# LED_Board.net
KiCad netlist of a schematic drawn in EAGLE
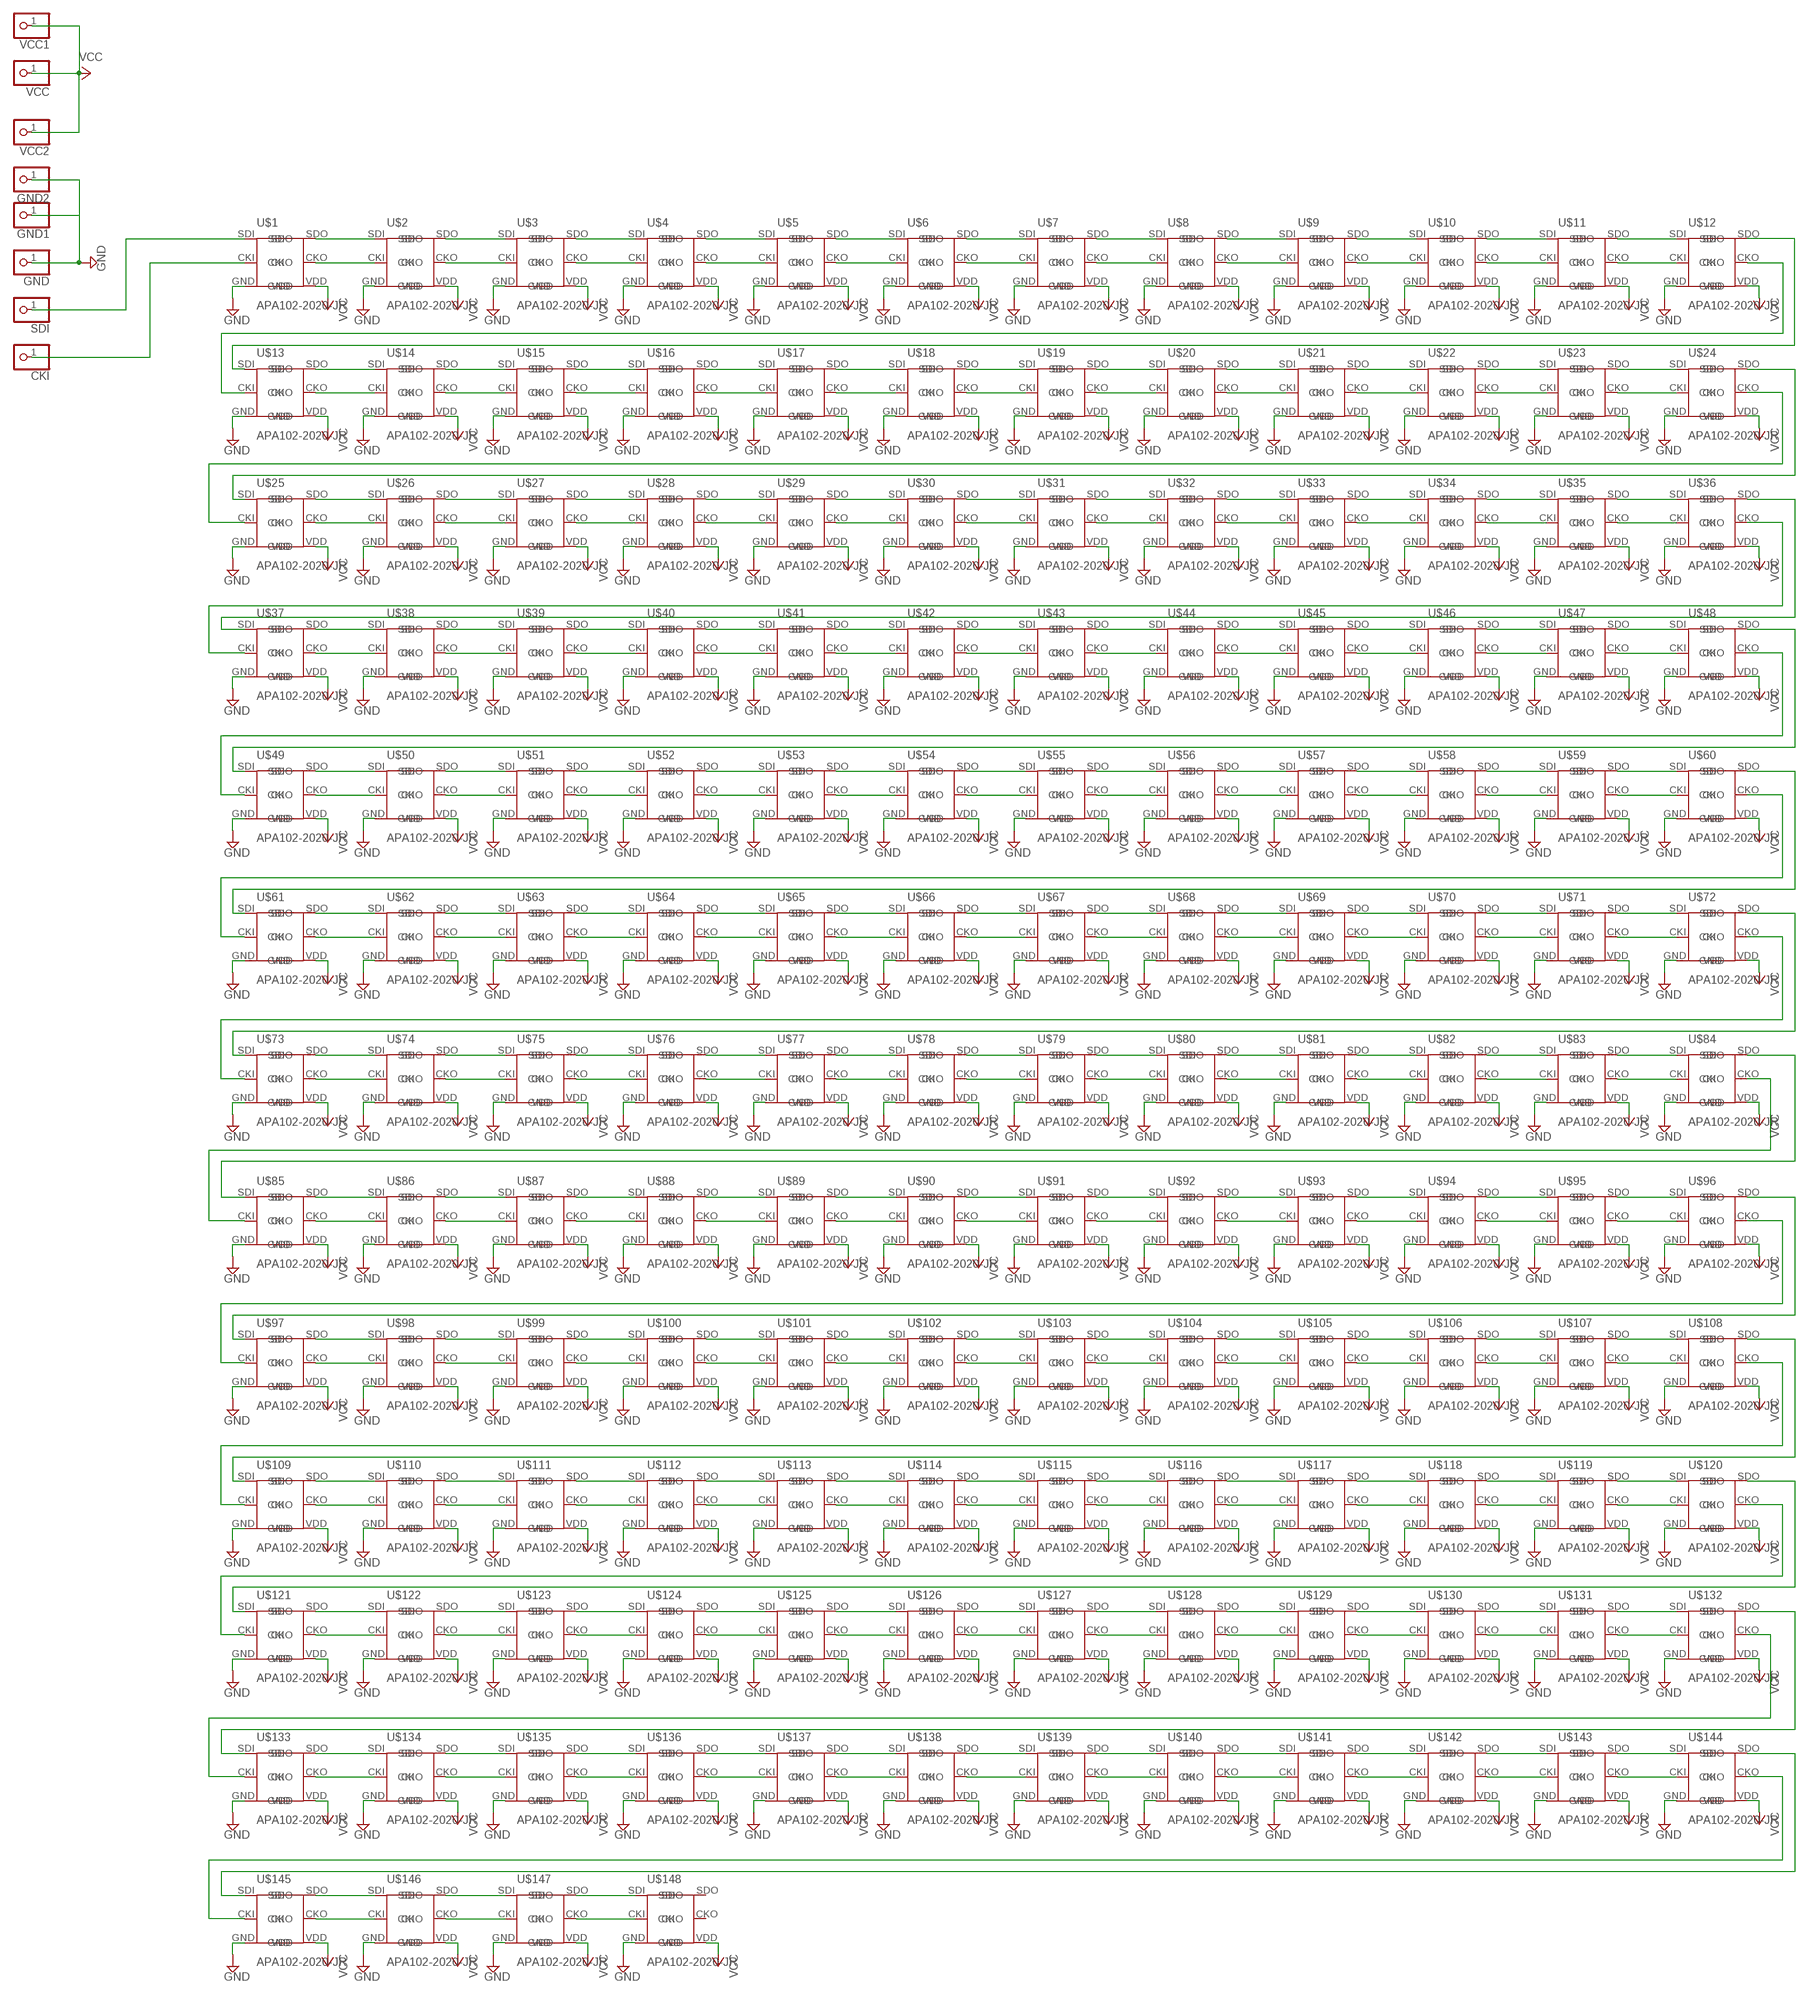
[diagram p0: schematic, sheet 1]

(export (version "E")
  (design (tool "Eeschema 10.0.6"))
  (components
    (comp (ref "CKI")
      (value "PINHD-1X1")
      (footprint "eagle-import:1X01")
      (libsource (lib "eagle-import") (part "PINHD-1X1"))
    )
    (comp (ref "GND")
      (value "PINHD-1X1")
      (footprint "eagle-import:1X01")
      (libsource (lib "eagle-import") (part "PINHD-1X1"))
    )
    (comp (ref "GND1")
      (value "PINHD-1X1")
      (footprint "eagle-import:1X01")
      (libsource (lib "eagle-import") (part "PINHD-1X1"))
    )
    (comp (ref "GND2")
      (value "PINHD-1X1")
      (footprint "eagle-import:1X01")
      (libsource (lib "eagle-import") (part "PINHD-1X1"))
    )
    (comp (ref "SDI")
      (value "PINHD-1X1")
      (footprint "eagle-import:1X01")
      (libsource (lib "eagle-import") (part "PINHD-1X1"))
    )
    (comp (ref "U$1")
      (value "APA102-2020-JR")
      (footprint "eagle-import:APA102-2020-JR")
      (libsource (lib "eagle-import") (part "APA102-2020-JR"))
    )
    (comp (ref "U$2")
      (value "APA102-2020-JR")
      (footprint "eagle-import:APA102-2020-JR")
      (libsource (lib "eagle-import") (part "APA102-2020-JR"))
    )
    (comp (ref "U$3")
      (value "APA102-2020-JR")
      (footprint "eagle-import:APA102-2020-JR")
      (libsource (lib "eagle-import") (part "APA102-2020-JR"))
    )
    (comp (ref "U$4")
      (value "APA102-2020-JR")
      (footprint "eagle-import:APA102-2020-JR")
      (libsource (lib "eagle-import") (part "APA102-2020-JR"))
    )
    (comp (ref "U$5")
      (value "APA102-2020-JR")
      (footprint "eagle-import:APA102-2020-JR")
      (libsource (lib "eagle-import") (part "APA102-2020-JR"))
    )
    (comp (ref "U$6")
      (value "APA102-2020-JR")
      (footprint "eagle-import:APA102-2020-JR")
      (libsource (lib "eagle-import") (part "APA102-2020-JR"))
    )
    (comp (ref "U$7")
      (value "APA102-2020-JR")
      (footprint "eagle-import:APA102-2020-JR")
      (libsource (lib "eagle-import") (part "APA102-2020-JR"))
    )
    (comp (ref "U$8")
      (value "APA102-2020-JR")
      (footprint "eagle-import:APA102-2020-JR")
      (libsource (lib "eagle-import") (part "APA102-2020-JR"))
    )
    (comp (ref "U$9")
      (value "APA102-2020-JR")
      (footprint "eagle-import:APA102-2020-JR")
      (libsource (lib "eagle-import") (part "APA102-2020-JR"))
    )
    (comp (ref "U$10")
      (value "APA102-2020-JR")
      (footprint "eagle-import:APA102-2020-JR")
      (libsource (lib "eagle-import") (part "APA102-2020-JR"))
    )
    (comp (ref "U$11")
      (value "APA102-2020-JR")
      (footprint "eagle-import:APA102-2020-JR")
      (libsource (lib "eagle-import") (part "APA102-2020-JR"))
    )
    (comp (ref "U$12")
      (value "APA102-2020-JR")
      (footprint "eagle-import:APA102-2020-JR")
      (libsource (lib "eagle-import") (part "APA102-2020-JR"))
    )
    (comp (ref "U$13")
      (value "APA102-2020-JR")
      (footprint "eagle-import:APA102-2020-JR")
      (libsource (lib "eagle-import") (part "APA102-2020-JR"))
    )
    (comp (ref "U$14")
      (value "APA102-2020-JR")
      (footprint "eagle-import:APA102-2020-JR")
      (libsource (lib "eagle-import") (part "APA102-2020-JR"))
    )
    (comp (ref "U$15")
      (value "APA102-2020-JR")
      (footprint "eagle-import:APA102-2020-JR")
      (libsource (lib "eagle-import") (part "APA102-2020-JR"))
    )
    (comp (ref "U$16")
      (value "APA102-2020-JR")
      (footprint "eagle-import:APA102-2020-JR")
      (libsource (lib "eagle-import") (part "APA102-2020-JR"))
    )
    (comp (ref "U$17")
      (value "APA102-2020-JR")
      (footprint "eagle-import:APA102-2020-JR")
      (libsource (lib "eagle-import") (part "APA102-2020-JR"))
    )
    (comp (ref "U$18")
      (value "APA102-2020-JR")
      (footprint "eagle-import:APA102-2020-JR")
      (libsource (lib "eagle-import") (part "APA102-2020-JR"))
    )
    (comp (ref "U$19")
      (value "APA102-2020-JR")
      (footprint "eagle-import:APA102-2020-JR")
      (libsource (lib "eagle-import") (part "APA102-2020-JR"))
    )
    (comp (ref "U$20")
      (value "APA102-2020-JR")
      (footprint "eagle-import:APA102-2020-JR")
      (libsource (lib "eagle-import") (part "APA102-2020-JR"))
    )
    (comp (ref "U$21")
      (value "APA102-2020-JR")
      (footprint "eagle-import:APA102-2020-JR")
      (libsource (lib "eagle-import") (part "APA102-2020-JR"))
    )
    (comp (ref "U$22")
      (value "APA102-2020-JR")
      (footprint "eagle-import:APA102-2020-JR")
      (libsource (lib "eagle-import") (part "APA102-2020-JR"))
    )
    (comp (ref "U$23")
      (value "APA102-2020-JR")
      (footprint "eagle-import:APA102-2020-JR")
      (libsource (lib "eagle-import") (part "APA102-2020-JR"))
    )
    (comp (ref "U$24")
      (value "APA102-2020-JR")
      (footprint "eagle-import:APA102-2020-JR")
      (libsource (lib "eagle-import") (part "APA102-2020-JR"))
    )
    (comp (ref "U$25")
      (value "APA102-2020-JR")
      (footprint "eagle-import:APA102-2020-JR")
      (libsource (lib "eagle-import") (part "APA102-2020-JR"))
    )
    (comp (ref "U$26")
      (value "APA102-2020-JR")
      (footprint "eagle-import:APA102-2020-JR")
      (libsource (lib "eagle-import") (part "APA102-2020-JR"))
    )
    (comp (ref "U$27")
      (value "APA102-2020-JR")
      (footprint "eagle-import:APA102-2020-JR")
      (libsource (lib "eagle-import") (part "APA102-2020-JR"))
    )
    (comp (ref "U$28")
      (value "APA102-2020-JR")
      (footprint "eagle-import:APA102-2020-JR")
      (libsource (lib "eagle-import") (part "APA102-2020-JR"))
    )
    (comp (ref "U$29")
      (value "APA102-2020-JR")
      (footprint "eagle-import:APA102-2020-JR")
      (libsource (lib "eagle-import") (part "APA102-2020-JR"))
    )
    (comp (ref "U$30")
      (value "APA102-2020-JR")
      (footprint "eagle-import:APA102-2020-JR")
      (libsource (lib "eagle-import") (part "APA102-2020-JR"))
    )
    (comp (ref "U$31")
      (value "APA102-2020-JR")
      (footprint "eagle-import:APA102-2020-JR")
      (libsource (lib "eagle-import") (part "APA102-2020-JR"))
    )
    (comp (ref "U$32")
      (value "APA102-2020-JR")
      (footprint "eagle-import:APA102-2020-JR")
      (libsource (lib "eagle-import") (part "APA102-2020-JR"))
    )
    (comp (ref "U$33")
      (value "APA102-2020-JR")
      (footprint "eagle-import:APA102-2020-JR")
      (libsource (lib "eagle-import") (part "APA102-2020-JR"))
    )
    (comp (ref "U$34")
      (value "APA102-2020-JR")
      (footprint "eagle-import:APA102-2020-JR")
      (libsource (lib "eagle-import") (part "APA102-2020-JR"))
    )
    (comp (ref "U$35")
      (value "APA102-2020-JR")
      (footprint "eagle-import:APA102-2020-JR")
      (libsource (lib "eagle-import") (part "APA102-2020-JR"))
    )
    (comp (ref "U$36")
      (value "APA102-2020-JR")
      (footprint "eagle-import:APA102-2020-JR")
      (libsource (lib "eagle-import") (part "APA102-2020-JR"))
    )
    (comp (ref "U$37")
      (value "APA102-2020-JR")
      (footprint "eagle-import:APA102-2020-JR")
      (libsource (lib "eagle-import") (part "APA102-2020-JR"))
    )
    (comp (ref "U$38")
      (value "APA102-2020-JR")
      (footprint "eagle-import:APA102-2020-JR")
      (libsource (lib "eagle-import") (part "APA102-2020-JR"))
    )
    (comp (ref "U$39")
      (value "APA102-2020-JR")
      (footprint "eagle-import:APA102-2020-JR")
      (libsource (lib "eagle-import") (part "APA102-2020-JR"))
    )
    (comp (ref "U$40")
      (value "APA102-2020-JR")
      (footprint "eagle-import:APA102-2020-JR")
      (libsource (lib "eagle-import") (part "APA102-2020-JR"))
    )
    (comp (ref "U$41")
      (value "APA102-2020-JR")
      (footprint "eagle-import:APA102-2020-JR")
      (libsource (lib "eagle-import") (part "APA102-2020-JR"))
    )
    (comp (ref "U$42")
      (value "APA102-2020-JR")
      (footprint "eagle-import:APA102-2020-JR")
      (libsource (lib "eagle-import") (part "APA102-2020-JR"))
    )
    (comp (ref "U$43")
      (value "APA102-2020-JR")
      (footprint "eagle-import:APA102-2020-JR")
      (libsource (lib "eagle-import") (part "APA102-2020-JR"))
    )
    (comp (ref "U$44")
      (value "APA102-2020-JR")
      (footprint "eagle-import:APA102-2020-JR")
      (libsource (lib "eagle-import") (part "APA102-2020-JR"))
    )
    (comp (ref "U$45")
      (value "APA102-2020-JR")
      (footprint "eagle-import:APA102-2020-JR")
      (libsource (lib "eagle-import") (part "APA102-2020-JR"))
    )
    (comp (ref "U$46")
      (value "APA102-2020-JR")
      (footprint "eagle-import:APA102-2020-JR")
      (libsource (lib "eagle-import") (part "APA102-2020-JR"))
    )
    (comp (ref "U$47")
      (value "APA102-2020-JR")
      (footprint "eagle-import:APA102-2020-JR")
      (libsource (lib "eagle-import") (part "APA102-2020-JR"))
    )
    (comp (ref "U$48")
      (value "APA102-2020-JR")
      (footprint "eagle-import:APA102-2020-JR")
      (libsource (lib "eagle-import") (part "APA102-2020-JR"))
    )
    (comp (ref "U$49")
      (value "APA102-2020-JR")
      (footprint "eagle-import:APA102-2020-JR")
      (libsource (lib "eagle-import") (part "APA102-2020-JR"))
    )
    (comp (ref "U$50")
      (value "APA102-2020-JR")
      (footprint "eagle-import:APA102-2020-JR")
      (libsource (lib "eagle-import") (part "APA102-2020-JR"))
    )
    (comp (ref "U$51")
      (value "APA102-2020-JR")
      (footprint "eagle-import:APA102-2020-JR")
      (libsource (lib "eagle-import") (part "APA102-2020-JR"))
    )
    (comp (ref "U$52")
      (value "APA102-2020-JR")
      (footprint "eagle-import:APA102-2020-JR")
      (libsource (lib "eagle-import") (part "APA102-2020-JR"))
    )
    (comp (ref "U$53")
      (value "APA102-2020-JR")
      (footprint "eagle-import:APA102-2020-JR")
      (libsource (lib "eagle-import") (part "APA102-2020-JR"))
    )
    (comp (ref "U$54")
      (value "APA102-2020-JR")
      (footprint "eagle-import:APA102-2020-JR")
      (libsource (lib "eagle-import") (part "APA102-2020-JR"))
    )
    (comp (ref "U$55")
      (value "APA102-2020-JR")
      (footprint "eagle-import:APA102-2020-JR")
      (libsource (lib "eagle-import") (part "APA102-2020-JR"))
    )
    (comp (ref "U$56")
      (value "APA102-2020-JR")
      (footprint "eagle-import:APA102-2020-JR")
      (libsource (lib "eagle-import") (part "APA102-2020-JR"))
    )
    (comp (ref "U$57")
      (value "APA102-2020-JR")
      (footprint "eagle-import:APA102-2020-JR")
      (libsource (lib "eagle-import") (part "APA102-2020-JR"))
    )
    (comp (ref "U$58")
      (value "APA102-2020-JR")
      (footprint "eagle-import:APA102-2020-JR")
      (libsource (lib "eagle-import") (part "APA102-2020-JR"))
    )
    (comp (ref "U$59")
      (value "APA102-2020-JR")
      (footprint "eagle-import:APA102-2020-JR")
      (libsource (lib "eagle-import") (part "APA102-2020-JR"))
    )
    (comp (ref "U$60")
      (value "APA102-2020-JR")
      (footprint "eagle-import:APA102-2020-JR")
      (libsource (lib "eagle-import") (part "APA102-2020-JR"))
    )
    (comp (ref "U$61")
      (value "APA102-2020-JR")
      (footprint "eagle-import:APA102-2020-JR")
      (libsource (lib "eagle-import") (part "APA102-2020-JR"))
    )
    (comp (ref "U$62")
      (value "APA102-2020-JR")
      (footprint "eagle-import:APA102-2020-JR")
      (libsource (lib "eagle-import") (part "APA102-2020-JR"))
    )
    (comp (ref "U$63")
      (value "APA102-2020-JR")
      (footprint "eagle-import:APA102-2020-JR")
      (libsource (lib "eagle-import") (part "APA102-2020-JR"))
    )
    (comp (ref "U$64")
      (value "APA102-2020-JR")
      (footprint "eagle-import:APA102-2020-JR")
      (libsource (lib "eagle-import") (part "APA102-2020-JR"))
    )
    (comp (ref "U$65")
      (value "APA102-2020-JR")
      (footprint "eagle-import:APA102-2020-JR")
      (libsource (lib "eagle-import") (part "APA102-2020-JR"))
    )
    (comp (ref "U$66")
      (value "APA102-2020-JR")
      (footprint "eagle-import:APA102-2020-JR")
      (libsource (lib "eagle-import") (part "APA102-2020-JR"))
    )
    (comp (ref "U$67")
      (value "APA102-2020-JR")
      (footprint "eagle-import:APA102-2020-JR")
      (libsource (lib "eagle-import") (part "APA102-2020-JR"))
    )
    (comp (ref "U$68")
      (value "APA102-2020-JR")
      (footprint "eagle-import:APA102-2020-JR")
      (libsource (lib "eagle-import") (part "APA102-2020-JR"))
    )
    (comp (ref "U$69")
      (value "APA102-2020-JR")
      (footprint "eagle-import:APA102-2020-JR")
      (libsource (lib "eagle-import") (part "APA102-2020-JR"))
    )
    (comp (ref "U$70")
      (value "APA102-2020-JR")
      (footprint "eagle-import:APA102-2020-JR")
      (libsource (lib "eagle-import") (part "APA102-2020-JR"))
    )
    (comp (ref "U$71")
      (value "APA102-2020-JR")
      (footprint "eagle-import:APA102-2020-JR")
      (libsource (lib "eagle-import") (part "APA102-2020-JR"))
    )
    (comp (ref "U$72")
      (value "APA102-2020-JR")
      (footprint "eagle-import:APA102-2020-JR")
      (libsource (lib "eagle-import") (part "APA102-2020-JR"))
    )
    (comp (ref "U$73")
      (value "APA102-2020-JR")
      (footprint "eagle-import:APA102-2020-JR")
      (libsource (lib "eagle-import") (part "APA102-2020-JR"))
    )
    (comp (ref "U$74")
      (value "APA102-2020-JR")
      (footprint "eagle-import:APA102-2020-JR")
      (libsource (lib "eagle-import") (part "APA102-2020-JR"))
    )
    (comp (ref "U$75")
      (value "APA102-2020-JR")
      (footprint "eagle-import:APA102-2020-JR")
      (libsource (lib "eagle-import") (part "APA102-2020-JR"))
    )
    (comp (ref "U$76")
      (value "APA102-2020-JR")
      (footprint "eagle-import:APA102-2020-JR")
      (libsource (lib "eagle-import") (part "APA102-2020-JR"))
    )
    (comp (ref "U$77")
      (value "APA102-2020-JR")
      (footprint "eagle-import:APA102-2020-JR")
      (libsource (lib "eagle-import") (part "APA102-2020-JR"))
    )
    (comp (ref "U$78")
      (value "APA102-2020-JR")
      (footprint "eagle-import:APA102-2020-JR")
      (libsource (lib "eagle-import") (part "APA102-2020-JR"))
    )
    (comp (ref "U$79")
      (value "APA102-2020-JR")
      (footprint "eagle-import:APA102-2020-JR")
      (libsource (lib "eagle-import") (part "APA102-2020-JR"))
    )
    (comp (ref "U$80")
      (value "APA102-2020-JR")
      (footprint "eagle-import:APA102-2020-JR")
      (libsource (lib "eagle-import") (part "APA102-2020-JR"))
    )
    (comp (ref "U$81")
      (value "APA102-2020-JR")
      (footprint "eagle-import:APA102-2020-JR")
      (libsource (lib "eagle-import") (part "APA102-2020-JR"))
    )
    (comp (ref "U$82")
      (value "APA102-2020-JR")
      (footprint "eagle-import:APA102-2020-JR")
      (libsource (lib "eagle-import") (part "APA102-2020-JR"))
    )
    (comp (ref "U$83")
      (value "APA102-2020-JR")
      (footprint "eagle-import:APA102-2020-JR")
      (libsource (lib "eagle-import") (part "APA102-2020-JR"))
    )
    (comp (ref "U$84")
      (value "APA102-2020-JR")
      (footprint "eagle-import:APA102-2020-JR")
      (libsource (lib "eagle-import") (part "APA102-2020-JR"))
    )
    (comp (ref "U$85")
      (value "APA102-2020-JR")
      (footprint "eagle-import:APA102-2020-JR")
      (libsource (lib "eagle-import") (part "APA102-2020-JR"))
    )
    (comp (ref "U$86")
      (value "APA102-2020-JR")
      (footprint "eagle-import:APA102-2020-JR")
      (libsource (lib "eagle-import") (part "APA102-2020-JR"))
    )
    (comp (ref "U$87")
      (value "APA102-2020-JR")
      (footprint "eagle-import:APA102-2020-JR")
      (libsource (lib "eagle-import") (part "APA102-2020-JR"))
    )
    (comp (ref "U$88")
      (value "APA102-2020-JR")
      (footprint "eagle-import:APA102-2020-JR")
      (libsource (lib "eagle-import") (part "APA102-2020-JR"))
    )
    (comp (ref "U$89")
      (value "APA102-2020-JR")
      (footprint "eagle-import:APA102-2020-JR")
      (libsource (lib "eagle-import") (part "APA102-2020-JR"))
    )
    (comp (ref "U$90")
      (value "APA102-2020-JR")
      (footprint "eagle-import:APA102-2020-JR")
      (libsource (lib "eagle-import") (part "APA102-2020-JR"))
    )
    (comp (ref "U$91")
      (value "APA102-2020-JR")
      (footprint "eagle-import:APA102-2020-JR")
      (libsource (lib "eagle-import") (part "APA102-2020-JR"))
    )
    (comp (ref "U$92")
      (value "APA102-2020-JR")
      (footprint "eagle-import:APA102-2020-JR")
      (libsource (lib "eagle-import") (part "APA102-2020-JR"))
    )
    (comp (ref "U$93")
      (value "APA102-2020-JR")
      (footprint "eagle-import:APA102-2020-JR")
      (libsource (lib "eagle-import") (part "APA102-2020-JR"))
    )
    (comp (ref "U$94")
      (value "APA102-2020-JR")
      (footprint "eagle-import:APA102-2020-JR")
      (libsource (lib "eagle-import") (part "APA102-2020-JR"))
    )
    (comp (ref "U$95")
      (value "APA102-2020-JR")
      (footprint "eagle-import:APA102-2020-JR")
      (libsource (lib "eagle-import") (part "APA102-2020-JR"))
    )
    (comp (ref "U$96")
      (value "APA102-2020-JR")
      (footprint "eagle-import:APA102-2020-JR")
      (libsource (lib "eagle-import") (part "APA102-2020-JR"))
    )
    (comp (ref "U$97")
      (value "APA102-2020-JR")
      (footprint "eagle-import:APA102-2020-JR")
      (libsource (lib "eagle-import") (part "APA102-2020-JR"))
    )
    (comp (ref "U$98")
      (value "APA102-2020-JR")
      (footprint "eagle-import:APA102-2020-JR")
      (libsource (lib "eagle-import") (part "APA102-2020-JR"))
    )
    (comp (ref "U$99")
      (value "APA102-2020-JR")
      (footprint "eagle-import:APA102-2020-JR")
      (libsource (lib "eagle-import") (part "APA102-2020-JR"))
    )
    (comp (ref "U$100")
      (value "APA102-2020-JR")
      (footprint "eagle-import:APA102-2020-JR")
      (libsource (lib "eagle-import") (part "APA102-2020-JR"))
    )
    (comp (ref "U$101")
      (value "APA102-2020-JR")
      (footprint "eagle-import:APA102-2020-JR")
      (libsource (lib "eagle-import") (part "APA102-2020-JR"))
    )
    (comp (ref "U$102")
      (value "APA102-2020-JR")
      (footprint "eagle-import:APA102-2020-JR")
      (libsource (lib "eagle-import") (part "APA102-2020-JR"))
    )
    (comp (ref "U$103")
      (value "APA102-2020-JR")
      (footprint "eagle-import:APA102-2020-JR")
      (libsource (lib "eagle-import") (part "APA102-2020-JR"))
    )
    (comp (ref "U$104")
      (value "APA102-2020-JR")
      (footprint "eagle-import:APA102-2020-JR")
      (libsource (lib "eagle-import") (part "APA102-2020-JR"))
    )
    (comp (ref "U$105")
      (value "APA102-2020-JR")
      (footprint "eagle-import:APA102-2020-JR")
      (libsource (lib "eagle-import") (part "APA102-2020-JR"))
    )
    (comp (ref "U$106")
      (value "APA102-2020-JR")
      (footprint "eagle-import:APA102-2020-JR")
      (libsource (lib "eagle-import") (part "APA102-2020-JR"))
    )
    (comp (ref "U$107")
      (value "APA102-2020-JR")
      (footprint "eagle-import:APA102-2020-JR")
      (libsource (lib "eagle-import") (part "APA102-2020-JR"))
    )
    (comp (ref "U$108")
      (value "APA102-2020-JR")
      (footprint "eagle-import:APA102-2020-JR")
      (libsource (lib "eagle-import") (part "APA102-2020-JR"))
    )
    (comp (ref "U$109")
      (value "APA102-2020-JR")
      (footprint "eagle-import:APA102-2020-JR")
      (libsource (lib "eagle-import") (part "APA102-2020-JR"))
    )
    (comp (ref "U$110")
      (value "APA102-2020-JR")
      (footprint "eagle-import:APA102-2020-JR")
      (libsource (lib "eagle-import") (part "APA102-2020-JR"))
    )
    (comp (ref "U$111")
      (value "APA102-2020-JR")
      (footprint "eagle-import:APA102-2020-JR")
      (libsource (lib "eagle-import") (part "APA102-2020-JR"))
    )
    (comp (ref "U$112")
      (value "APA102-2020-JR")
      (footprint "eagle-import:APA102-2020-JR")
      (libsource (lib "eagle-import") (part "APA102-2020-JR"))
    )
    (comp (ref "U$113")
      (value "APA102-2020-JR")
      (footprint "eagle-import:APA102-2020-JR")
      (libsource (lib "eagle-import") (part "APA102-2020-JR"))
    )
    (comp (ref "U$114")
      (value "APA102-2020-JR")
      (footprint "eagle-import:APA102-2020-JR")
      (libsource (lib "eagle-import") (part "APA102-2020-JR"))
    )
    (comp (ref "U$115")
      (value "APA102-2020-JR")
      (footprint "eagle-import:APA102-2020-JR")
      (libsource (lib "eagle-import") (part "APA102-2020-JR"))
    )
    (comp (ref "U$116")
      (value "APA102-2020-JR")
      (footprint "eagle-import:APA102-2020-JR")
      (libsource (lib "eagle-import") (part "APA102-2020-JR"))
    )
    (comp (ref "U$117")
      (value "APA102-2020-JR")
      (footprint "eagle-import:APA102-2020-JR")
      (libsource (lib "eagle-import") (part "APA102-2020-JR"))
    )
    (comp (ref "U$118")
      (value "APA102-2020-JR")
      (footprint "eagle-import:APA102-2020-JR")
      (libsource (lib "eagle-import") (part "APA102-2020-JR"))
    )
    (comp (ref "U$119")
      (value "APA102-2020-JR")
      (footprint "eagle-import:APA102-2020-JR")
      (libsource (lib "eagle-import") (part "APA102-2020-JR"))
    )
    (comp (ref "U$120")
      (value "APA102-2020-JR")
      (footprint "eagle-import:APA102-2020-JR")
      (libsource (lib "eagle-import") (part "APA102-2020-JR"))
    )
    (comp (ref "U$121")
      (value "APA102-2020-JR")
      (footprint "eagle-import:APA102-2020-JR")
      (libsource (lib "eagle-import") (part "APA102-2020-JR"))
    )
    (comp (ref "U$122")
      (value "APA102-2020-JR")
      (footprint "eagle-import:APA102-2020-JR")
      (libsource (lib "eagle-import") (part "APA102-2020-JR"))
    )
    (comp (ref "U$123")
      (value "APA102-2020-JR")
      (footprint "eagle-import:APA102-2020-JR")
      (libsource (lib "eagle-import") (part "APA102-2020-JR"))
    )
    (comp (ref "U$124")
      (value "APA102-2020-JR")
      (footprint "eagle-import:APA102-2020-JR")
      (libsource (lib "eagle-import") (part "APA102-2020-JR"))
    )
    (comp (ref "U$125")
      (value "APA102-2020-JR")
      (footprint "eagle-import:APA102-2020-JR")
      (libsource (lib "eagle-import") (part "APA102-2020-JR"))
    )
    (comp (ref "U$126")
      (value "APA102-2020-JR")
      (footprint "eagle-import:APA102-2020-JR")
      (libsource (lib "eagle-import") (part "APA102-2020-JR"))
    )
    (comp (ref "U$127")
      (value "APA102-2020-JR")
      (footprint "eagle-import:APA102-2020-JR")
      (libsource (lib "eagle-import") (part "APA102-2020-JR"))
    )
    (comp (ref "U$128")
      (value "APA102-2020-JR")
      (footprint "eagle-import:APA102-2020-JR")
      (libsource (lib "eagle-import") (part "APA102-2020-JR"))
    )
    (comp (ref "U$129")
      (value "APA102-2020-JR")
      (footprint "eagle-import:APA102-2020-JR")
      (libsource (lib "eagle-import") (part "APA102-2020-JR"))
    )
    (comp (ref "U$130")
      (value "APA102-2020-JR")
      (footprint "eagle-import:APA102-2020-JR")
      (libsource (lib "eagle-import") (part "APA102-2020-JR"))
    )
    (comp (ref "U$131")
      (value "APA102-2020-JR")
      (footprint "eagle-import:APA102-2020-JR")
      (libsource (lib "eagle-import") (part "APA102-2020-JR"))
    )
    (comp (ref "U$132")
      (value "APA102-2020-JR")
      (footprint "eagle-import:APA102-2020-JR")
      (libsource (lib "eagle-import") (part "APA102-2020-JR"))
    )
    (comp (ref "U$133")
      (value "APA102-2020-JR")
      (footprint "eagle-import:APA102-2020-JR")
      (libsource (lib "eagle-import") (part "APA102-2020-JR"))
    )
    (comp (ref "U$134")
      (value "APA102-2020-JR")
      (footprint "eagle-import:APA102-2020-JR")
      (libsource (lib "eagle-import") (part "APA102-2020-JR"))
    )
    (comp (ref "U$135")
      (value "APA102-2020-JR")
      (footprint "eagle-import:APA102-2020-JR")
      (libsource (lib "eagle-import") (part "APA102-2020-JR"))
    )
    (comp (ref "U$136")
      (value "APA102-2020-JR")
      (footprint "eagle-import:APA102-2020-JR")
      (libsource (lib "eagle-import") (part "APA102-2020-JR"))
    )
    (comp (ref "U$137")
      (value "APA102-2020-JR")
      (footprint "eagle-import:APA102-2020-JR")
      (libsource (lib "eagle-import") (part "APA102-2020-JR"))
    )
    (comp (ref "U$138")
      (value "APA102-2020-JR")
      (footprint "eagle-import:APA102-2020-JR")
      (libsource (lib "eagle-import") (part "APA102-2020-JR"))
    )
    (comp (ref "U$139")
      (value "APA102-2020-JR")
      (footprint "eagle-import:APA102-2020-JR")
      (libsource (lib "eagle-import") (part "APA102-2020-JR"))
    )
    (comp (ref "U$140")
      (value "APA102-2020-JR")
      (footprint "eagle-import:APA102-2020-JR")
      (libsource (lib "eagle-import") (part "APA102-2020-JR"))
    )
    (comp (ref "U$141")
      (value "APA102-2020-JR")
      (footprint "eagle-import:APA102-2020-JR")
      (libsource (lib "eagle-import") (part "APA102-2020-JR"))
    )
    (comp (ref "U$142")
      (value "APA102-2020-JR")
      (footprint "eagle-import:APA102-2020-JR")
      (libsource (lib "eagle-import") (part "APA102-2020-JR"))
    )
    (comp (ref "U$143")
      (value "APA102-2020-JR")
      (footprint "eagle-import:APA102-2020-JR")
      (libsource (lib "eagle-import") (part "APA102-2020-JR"))
    )
    (comp (ref "U$144")
      (value "APA102-2020-JR")
      (footprint "eagle-import:APA102-2020-JR")
      (libsource (lib "eagle-import") (part "APA102-2020-JR"))
    )
    (comp (ref "U$145")
      (value "APA102-2020-JR")
      (footprint "eagle-import:APA102-2020-JR")
      (libsource (lib "eagle-import") (part "APA102-2020-JR"))
    )
    (comp (ref "U$146")
      (value "APA102-2020-JR")
      (footprint "eagle-import:APA102-2020-JR")
      (libsource (lib "eagle-import") (part "APA102-2020-JR"))
    )
    (comp (ref "U$147")
      (value "APA102-2020-JR")
      (footprint "eagle-import:APA102-2020-JR")
      (libsource (lib "eagle-import") (part "APA102-2020-JR"))
    )
    (comp (ref "U$148")
      (value "APA102-2020-JR")
      (footprint "eagle-import:APA102-2020-JR")
      (libsource (lib "eagle-import") (part "APA102-2020-JR"))
    )
    (comp (ref "VCC")
      (value "PINHD-1X1")
      (footprint "eagle-import:1X01")
      (libsource (lib "eagle-import") (part "PINHD-1X1"))
    )
    (comp (ref "VCC1")
      (value "PINHD-1X1")
      (footprint "eagle-import:1X01")
      (libsource (lib "eagle-import") (part "PINHD-1X1"))
    )
    (comp (ref "VCC2")
      (value "PINHD-1X1")
      (footprint "eagle-import:1X01")
      (libsource (lib "eagle-import") (part "PINHD-1X1"))
    )
  )
  (nets
    (net (code "1") (name "GND") (class "Default")
      (node (ref "GND") (pin "1") (pinfunction "1_1") (pintype "passive"))
      (node (ref "GND1") (pin "1") (pinfunction "1_1") (pintype "passive"))
      (node (ref "GND2") (pin "1") (pinfunction "1_1") (pintype "passive"))
      (node (ref "U$1") (pin "GND") (pinfunction "GND_GND") (pintype "bidirectional"))
      (node (ref "U$10") (pin "GND") (pinfunction "GND_GND") (pintype "bidirectional"))
      (node (ref "U$100") (pin "GND") (pinfunction "GND_GND") (pintype "bidirectional"))
      (node (ref "U$101") (pin "GND") (pinfunction "GND_GND") (pintype "bidirectional"))
      (node (ref "U$102") (pin "GND") (pinfunction "GND_GND") (pintype "bidirectional"))
      (node (ref "U$103") (pin "GND") (pinfunction "GND_GND") (pintype "bidirectional"))
      (node (ref "U$104") (pin "GND") (pinfunction "GND_GND") (pintype "bidirectional"))
      (node (ref "U$105") (pin "GND") (pinfunction "GND_GND") (pintype "bidirectional"))
      (node (ref "U$106") (pin "GND") (pinfunction "GND_GND") (pintype "bidirectional"))
      (node (ref "U$107") (pin "GND") (pinfunction "GND_GND") (pintype "bidirectional"))
      (node (ref "U$108") (pin "GND") (pinfunction "GND_GND") (pintype "bidirectional"))
      (node (ref "U$109") (pin "GND") (pinfunction "GND_GND") (pintype "bidirectional"))
      (node (ref "U$11") (pin "GND") (pinfunction "GND_GND") (pintype "bidirectional"))
      (node (ref "U$110") (pin "GND") (pinfunction "GND_GND") (pintype "bidirectional"))
      (node (ref "U$111") (pin "GND") (pinfunction "GND_GND") (pintype "bidirectional"))
      (node (ref "U$112") (pin "GND") (pinfunction "GND_GND") (pintype "bidirectional"))
      (node (ref "U$113") (pin "GND") (pinfunction "GND_GND") (pintype "bidirectional"))
      (node (ref "U$114") (pin "GND") (pinfunction "GND_GND") (pintype "bidirectional"))
      (node (ref "U$115") (pin "GND") (pinfunction "GND_GND") (pintype "bidirectional"))
      (node (ref "U$116") (pin "GND") (pinfunction "GND_GND") (pintype "bidirectional"))
      (node (ref "U$117") (pin "GND") (pinfunction "GND_GND") (pintype "bidirectional"))
      (node (ref "U$118") (pin "GND") (pinfunction "GND_GND") (pintype "bidirectional"))
      (node (ref "U$119") (pin "GND") (pinfunction "GND_GND") (pintype "bidirectional"))
      (node (ref "U$12") (pin "GND") (pinfunction "GND_GND") (pintype "bidirectional"))
      (node (ref "U$120") (pin "GND") (pinfunction "GND_GND") (pintype "bidirectional"))
      (node (ref "U$121") (pin "GND") (pinfunction "GND_GND") (pintype "bidirectional"))
      (node (ref "U$122") (pin "GND") (pinfunction "GND_GND") (pintype "bidirectional"))
      (node (ref "U$123") (pin "GND") (pinfunction "GND_GND") (pintype "bidirectional"))
      (node (ref "U$124") (pin "GND") (pinfunction "GND_GND") (pintype "bidirectional"))
      (node (ref "U$125") (pin "GND") (pinfunction "GND_GND") (pintype "bidirectional"))
      (node (ref "U$126") (pin "GND") (pinfunction "GND_GND") (pintype "bidirectional"))
      (node (ref "U$127") (pin "GND") (pinfunction "GND_GND") (pintype "bidirectional"))
      (node (ref "U$128") (pin "GND") (pinfunction "GND_GND") (pintype "bidirectional"))
      (node (ref "U$129") (pin "GND") (pinfunction "GND_GND") (pintype "bidirectional"))
      (node (ref "U$13") (pin "GND") (pinfunction "GND_GND") (pintype "bidirectional"))
      (node (ref "U$130") (pin "GND") (pinfunction "GND_GND") (pintype "bidirectional"))
      (node (ref "U$131") (pin "GND") (pinfunction "GND_GND") (pintype "bidirectional"))
      (node (ref "U$132") (pin "GND") (pinfunction "GND_GND") (pintype "bidirectional"))
      (node (ref "U$133") (pin "GND") (pinfunction "GND_GND") (pintype "bidirectional"))
      (node (ref "U$134") (pin "GND") (pinfunction "GND_GND") (pintype "bidirectional"))
      (node (ref "U$135") (pin "GND") (pinfunction "GND_GND") (pintype "bidirectional"))
      (node (ref "U$136") (pin "GND") (pinfunction "GND_GND") (pintype "bidirectional"))
      (node (ref "U$137") (pin "GND") (pinfunction "GND_GND") (pintype "bidirectional"))
      (node (ref "U$138") (pin "GND") (pinfunction "GND_GND") (pintype "bidirectional"))
      (node (ref "U$139") (pin "GND") (pinfunction "GND_GND") (pintype "bidirectional"))
      (node (ref "U$14") (pin "GND") (pinfunction "GND_GND") (pintype "bidirectional"))
      (node (ref "U$140") (pin "GND") (pinfunction "GND_GND") (pintype "bidirectional"))
      (node (ref "U$141") (pin "GND") (pinfunction "GND_GND") (pintype "bidirectional"))
      (node (ref "U$142") (pin "GND") (pinfunction "GND_GND") (pintype "bidirectional"))
      (node (ref "U$143") (pin "GND") (pinfunction "GND_GND") (pintype "bidirectional"))
      (node (ref "U$144") (pin "GND") (pinfunction "GND_GND") (pintype "bidirectional"))
      (node (ref "U$145") (pin "GND") (pinfunction "GND_GND") (pintype "bidirectional"))
      (node (ref "U$146") (pin "GND") (pinfunction "GND_GND") (pintype "bidirectional"))
      (node (ref "U$147") (pin "GND") (pinfunction "GND_GND") (pintype "bidirectional"))
      (node (ref "U$148") (pin "GND") (pinfunction "GND_GND") (pintype "bidirectional"))
      (node (ref "U$15") (pin "GND") (pinfunction "GND_GND") (pintype "bidirectional"))
      (node (ref "U$16") (pin "GND") (pinfunction "GND_GND") (pintype "bidirectional"))
      (node (ref "U$17") (pin "GND") (pinfunction "GND_GND") (pintype "bidirectional"))
      (node (ref "U$18") (pin "GND") (pinfunction "GND_GND") (pintype "bidirectional"))
      (node (ref "U$19") (pin "GND") (pinfunction "GND_GND") (pintype "bidirectional"))
      (node (ref "U$2") (pin "GND") (pinfunction "GND_GND") (pintype "bidirectional"))
      (node (ref "U$20") (pin "GND") (pinfunction "GND_GND") (pintype "bidirectional"))
      (node (ref "U$21") (pin "GND") (pinfunction "GND_GND") (pintype "bidirectional"))
      (node (ref "U$22") (pin "GND") (pinfunction "GND_GND") (pintype "bidirectional"))
      (node (ref "U$23") (pin "GND") (pinfunction "GND_GND") (pintype "bidirectional"))
      (node (ref "U$24") (pin "GND") (pinfunction "GND_GND") (pintype "bidirectional"))
      (node (ref "U$25") (pin "GND") (pinfunction "GND_GND") (pintype "bidirectional"))
      (node (ref "U$26") (pin "GND") (pinfunction "GND_GND") (pintype "bidirectional"))
      (node (ref "U$27") (pin "GND") (pinfunction "GND_GND") (pintype "bidirectional"))
      (node (ref "U$28") (pin "GND") (pinfunction "GND_GND") (pintype "bidirectional"))
      (node (ref "U$29") (pin "GND") (pinfunction "GND_GND") (pintype "bidirectional"))
      (node (ref "U$3") (pin "GND") (pinfunction "GND_GND") (pintype "bidirectional"))
      (node (ref "U$30") (pin "GND") (pinfunction "GND_GND") (pintype "bidirectional"))
      (node (ref "U$31") (pin "GND") (pinfunction "GND_GND") (pintype "bidirectional"))
      (node (ref "U$32") (pin "GND") (pinfunction "GND_GND") (pintype "bidirectional"))
      (node (ref "U$33") (pin "GND") (pinfunction "GND_GND") (pintype "bidirectional"))
      (node (ref "U$34") (pin "GND") (pinfunction "GND_GND") (pintype "bidirectional"))
      (node (ref "U$35") (pin "GND") (pinfunction "GND_GND") (pintype "bidirectional"))
      (node (ref "U$36") (pin "GND") (pinfunction "GND_GND") (pintype "bidirectional"))
      (node (ref "U$37") (pin "GND") (pinfunction "GND_GND") (pintype "bidirectional"))
      (node (ref "U$38") (pin "GND") (pinfunction "GND_GND") (pintype "bidirectional"))
      (node (ref "U$39") (pin "GND") (pinfunction "GND_GND") (pintype "bidirectional"))
      (node (ref "U$4") (pin "GND") (pinfunction "GND_GND") (pintype "bidirectional"))
      (node (ref "U$40") (pin "GND") (pinfunction "GND_GND") (pintype "bidirectional"))
      (node (ref "U$41") (pin "GND") (pinfunction "GND_GND") (pintype "bidirectional"))
      (node (ref "U$42") (pin "GND") (pinfunction "GND_GND") (pintype "bidirectional"))
      (node (ref "U$43") (pin "GND") (pinfunction "GND_GND") (pintype "bidirectional"))
      (node (ref "U$44") (pin "GND") (pinfunction "GND_GND") (pintype "bidirectional"))
      (node (ref "U$45") (pin "GND") (pinfunction "GND_GND") (pintype "bidirectional"))
      (node (ref "U$46") (pin "GND") (pinfunction "GND_GND") (pintype "bidirectional"))
      (node (ref "U$47") (pin "GND") (pinfunction "GND_GND") (pintype "bidirectional"))
      (node (ref "U$48") (pin "GND") (pinfunction "GND_GND") (pintype "bidirectional"))
      (node (ref "U$49") (pin "GND") (pinfunction "GND_GND") (pintype "bidirectional"))
      (node (ref "U$5") (pin "GND") (pinfunction "GND_GND") (pintype "bidirectional"))
      (node (ref "U$50") (pin "GND") (pinfunction "GND_GND") (pintype "bidirectional"))
      (node (ref "U$51") (pin "GND") (pinfunction "GND_GND") (pintype "bidirectional"))
      (node (ref "U$52") (pin "GND") (pinfunction "GND_GND") (pintype "bidirectional"))
      (node (ref "U$53") (pin "GND") (pinfunction "GND_GND") (pintype "bidirectional"))
      (node (ref "U$54") (pin "GND") (pinfunction "GND_GND") (pintype "bidirectional"))
      (node (ref "U$55") (pin "GND") (pinfunction "GND_GND") (pintype "bidirectional"))
      (node (ref "U$56") (pin "GND") (pinfunction "GND_GND") (pintype "bidirectional"))
      (node (ref "U$57") (pin "GND") (pinfunction "GND_GND") (pintype "bidirectional"))
      (node (ref "U$58") (pin "GND") (pinfunction "GND_GND") (pintype "bidirectional"))
      (node (ref "U$59") (pin "GND") (pinfunction "GND_GND") (pintype "bidirectional"))
      (node (ref "U$6") (pin "GND") (pinfunction "GND_GND") (pintype "bidirectional"))
      (node (ref "U$60") (pin "GND") (pinfunction "GND_GND") (pintype "bidirectional"))
      (node (ref "U$61") (pin "GND") (pinfunction "GND_GND") (pintype "bidirectional"))
      (node (ref "U$62") (pin "GND") (pinfunction "GND_GND") (pintype "bidirectional"))
      (node (ref "U$63") (pin "GND") (pinfunction "GND_GND") (pintype "bidirectional"))
      (node (ref "U$64") (pin "GND") (pinfunction "GND_GND") (pintype "bidirectional"))
      (node (ref "U$65") (pin "GND") (pinfunction "GND_GND") (pintype "bidirectional"))
      (node (ref "U$66") (pin "GND") (pinfunction "GND_GND") (pintype "bidirectional"))
      (node (ref "U$67") (pin "GND") (pinfunction "GND_GND") (pintype "bidirectional"))
      (node (ref "U$68") (pin "GND") (pinfunction "GND_GND") (pintype "bidirectional"))
      (node (ref "U$69") (pin "GND") (pinfunction "GND_GND") (pintype "bidirectional"))
      (node (ref "U$7") (pin "GND") (pinfunction "GND_GND") (pintype "bidirectional"))
      (node (ref "U$70") (pin "GND") (pinfunction "GND_GND") (pintype "bidirectional"))
      (node (ref "U$71") (pin "GND") (pinfunction "GND_GND") (pintype "bidirectional"))
      (node (ref "U$72") (pin "GND") (pinfunction "GND_GND") (pintype "bidirectional"))
      (node (ref "U$73") (pin "GND") (pinfunction "GND_GND") (pintype "bidirectional"))
      (node (ref "U$74") (pin "GND") (pinfunction "GND_GND") (pintype "bidirectional"))
      (node (ref "U$75") (pin "GND") (pinfunction "GND_GND") (pintype "bidirectional"))
      (node (ref "U$76") (pin "GND") (pinfunction "GND_GND") (pintype "bidirectional"))
      (node (ref "U$77") (pin "GND") (pinfunction "GND_GND") (pintype "bidirectional"))
      (node (ref "U$78") (pin "GND") (pinfunction "GND_GND") (pintype "bidirectional"))
      (node (ref "U$79") (pin "GND") (pinfunction "GND_GND") (pintype "bidirectional"))
      (node (ref "U$8") (pin "GND") (pinfunction "GND_GND") (pintype "bidirectional"))
      (node (ref "U$80") (pin "GND") (pinfunction "GND_GND") (pintype "bidirectional"))
      (node (ref "U$81") (pin "GND") (pinfunction "GND_GND") (pintype "bidirectional"))
      (node (ref "U$82") (pin "GND") (pinfunction "GND_GND") (pintype "bidirectional"))
      (node (ref "U$83") (pin "GND") (pinfunction "GND_GND") (pintype "bidirectional"))
      (node (ref "U$84") (pin "GND") (pinfunction "GND_GND") (pintype "bidirectional"))
      (node (ref "U$85") (pin "GND") (pinfunction "GND_GND") (pintype "bidirectional"))
      (node (ref "U$86") (pin "GND") (pinfunction "GND_GND") (pintype "bidirectional"))
      (node (ref "U$87") (pin "GND") (pinfunction "GND_GND") (pintype "bidirectional"))
      (node (ref "U$88") (pin "GND") (pinfunction "GND_GND") (pintype "bidirectional"))
      (node (ref "U$89") (pin "GND") (pinfunction "GND_GND") (pintype "bidirectional"))
      (node (ref "U$9") (pin "GND") (pinfunction "GND_GND") (pintype "bidirectional"))
      (node (ref "U$90") (pin "GND") (pinfunction "GND_GND") (pintype "bidirectional"))
      (node (ref "U$91") (pin "GND") (pinfunction "GND_GND") (pintype "bidirectional"))
      (node (ref "U$92") (pin "GND") (pinfunction "GND_GND") (pintype "bidirectional"))
      (node (ref "U$93") (pin "GND") (pinfunction "GND_GND") (pintype "bidirectional"))
      (node (ref "U$94") (pin "GND") (pinfunction "GND_GND") (pintype "bidirectional"))
      (node (ref "U$95") (pin "GND") (pinfunction "GND_GND") (pintype "bidirectional"))
      (node (ref "U$96") (pin "GND") (pinfunction "GND_GND") (pintype "bidirectional"))
      (node (ref "U$97") (pin "GND") (pinfunction "GND_GND") (pintype "bidirectional"))
      (node (ref "U$98") (pin "GND") (pinfunction "GND_GND") (pintype "bidirectional"))
      (node (ref "U$99") (pin "GND") (pinfunction "GND_GND") (pintype "bidirectional"))
    )
    (net (code "2") (name "Net-(CKI-Pad1)") (class "Default")
      (node (ref "CKI") (pin "1") (pinfunction "1_1") (pintype "passive"))
      (node (ref "U$1") (pin "CKI") (pinfunction "CKI_CKI") (pintype "bidirectional"))
    )
    (net (code "3") (name "Net-(SDI-Pad1)") (class "Default")
      (node (ref "SDI") (pin "1") (pinfunction "1_1") (pintype "passive"))
      (node (ref "U$1") (pin "SDI") (pinfunction "SDI_SDI") (pintype "bidirectional"))
    )
    (net (code "4") (name "Net-(U$1-PadCKO)") (class "Default")
      (node (ref "U$1") (pin "CKO") (pinfunction "CKO_CKO") (pintype "bidirectional"))
      (node (ref "U$2") (pin "CKI") (pinfunction "CKI_CKI") (pintype "bidirectional"))
    )
    (net (code "5") (name "Net-(U$1-PadSDO)") (class "Default")
      (node (ref "U$1") (pin "SDO") (pinfunction "SDO_SDO") (pintype "bidirectional"))
      (node (ref "U$2") (pin "SDI") (pinfunction "SDI_SDI") (pintype "bidirectional"))
    )
    (net (code "6") (name "Net-(U$2-PadCKO)") (class "Default")
      (node (ref "U$2") (pin "CKO") (pinfunction "CKO_CKO") (pintype "bidirectional"))
      (node (ref "U$3") (pin "CKI") (pinfunction "CKI_CKI") (pintype "bidirectional"))
    )
    (net (code "7") (name "Net-(U$2-PadSDO)") (class "Default")
      (node (ref "U$2") (pin "SDO") (pinfunction "SDO_SDO") (pintype "bidirectional"))
      (node (ref "U$3") (pin "SDI") (pinfunction "SDI_SDI") (pintype "bidirectional"))
    )
    (net (code "8") (name "Net-(U$3-PadCKO)") (class "Default")
      (node (ref "U$3") (pin "CKO") (pinfunction "CKO_CKO") (pintype "bidirectional"))
      (node (ref "U$4") (pin "CKI") (pinfunction "CKI_CKI") (pintype "bidirectional"))
    )
    (net (code "9") (name "Net-(U$3-PadSDO)") (class "Default")
      (node (ref "U$3") (pin "SDO") (pinfunction "SDO_SDO") (pintype "bidirectional"))
      (node (ref "U$4") (pin "SDI") (pinfunction "SDI_SDI") (pintype "bidirectional"))
    )
    (net (code "10") (name "Net-(U$4-PadCKO)") (class "Default")
      (node (ref "U$4") (pin "CKO") (pinfunction "CKO_CKO") (pintype "bidirectional"))
      (node (ref "U$5") (pin "CKI") (pinfunction "CKI_CKI") (pintype "bidirectional"))
    )
    (net (code "11") (name "Net-(U$4-PadSDO)") (class "Default")
      (node (ref "U$4") (pin "SDO") (pinfunction "SDO_SDO") (pintype "bidirectional"))
      (node (ref "U$5") (pin "SDI") (pinfunction "SDI_SDI") (pintype "bidirectional"))
    )
    (net (code "12") (name "Net-(U$5-PadCKO)") (class "Default")
      (node (ref "U$5") (pin "CKO") (pinfunction "CKO_CKO") (pintype "bidirectional"))
      (node (ref "U$6") (pin "CKI") (pinfunction "CKI_CKI") (pintype "bidirectional"))
    )
    (net (code "13") (name "Net-(U$5-PadSDO)") (class "Default")
      (node (ref "U$5") (pin "SDO") (pinfunction "SDO_SDO") (pintype "bidirectional"))
      (node (ref "U$6") (pin "SDI") (pinfunction "SDI_SDI") (pintype "bidirectional"))
    )
    (net (code "14") (name "Net-(U$6-PadCKO)") (class "Default")
      (node (ref "U$6") (pin "CKO") (pinfunction "CKO_CKO") (pintype "bidirectional"))
      (node (ref "U$7") (pin "CKI") (pinfunction "CKI_CKI") (pintype "bidirectional"))
    )
    (net (code "15") (name "Net-(U$6-PadSDO)") (class "Default")
      (node (ref "U$6") (pin "SDO") (pinfunction "SDO_SDO") (pintype "bidirectional"))
      (node (ref "U$7") (pin "SDI") (pinfunction "SDI_SDI") (pintype "bidirectional"))
    )
    (net (code "16") (name "Net-(U$7-PadCKO)") (class "Default")
      (node (ref "U$7") (pin "CKO") (pinfunction "CKO_CKO") (pintype "bidirectional"))
      (node (ref "U$8") (pin "CKI") (pinfunction "CKI_CKI") (pintype "bidirectional"))
    )
    (net (code "17") (name "Net-(U$7-PadSDO)") (class "Default")
      (node (ref "U$7") (pin "SDO") (pinfunction "SDO_SDO") (pintype "bidirectional"))
      (node (ref "U$8") (pin "SDI") (pinfunction "SDI_SDI") (pintype "bidirectional"))
    )
    (net (code "18") (name "Net-(U$8-PadCKO)") (class "Default")
      (node (ref "U$8") (pin "CKO") (pinfunction "CKO_CKO") (pintype "bidirectional"))
      (node (ref "U$9") (pin "CKI") (pinfunction "CKI_CKI") (pintype "bidirectional"))
    )
    (net (code "19") (name "Net-(U$8-PadSDO)") (class "Default")
      (node (ref "U$8") (pin "SDO") (pinfunction "SDO_SDO") (pintype "bidirectional"))
      (node (ref "U$9") (pin "SDI") (pinfunction "SDI_SDI") (pintype "bidirectional"))
    )
    (net (code "20") (name "Net-(U$10-PadCKI)") (class "Default")
      (node (ref "U$10") (pin "CKI") (pinfunction "CKI_CKI") (pintype "bidirectional"))
      (node (ref "U$9") (pin "CKO") (pinfunction "CKO_CKO") (pintype "bidirectional"))
    )
    (net (code "21") (name "Net-(U$10-PadCKO)") (class "Default")
      (node (ref "U$10") (pin "CKO") (pinfunction "CKO_CKO") (pintype "bidirectional"))
      (node (ref "U$11") (pin "CKI") (pinfunction "CKI_CKI") (pintype "bidirectional"))
    )
    (net (code "22") (name "Net-(U$10-PadSDI)") (class "Default")
      (node (ref "U$10") (pin "SDI") (pinfunction "SDI_SDI") (pintype "bidirectional"))
      (node (ref "U$9") (pin "SDO") (pinfunction "SDO_SDO") (pintype "bidirectional"))
    )
    (net (code "23") (name "Net-(U$10-PadSDO)") (class "Default")
      (node (ref "U$10") (pin "SDO") (pinfunction "SDO_SDO") (pintype "bidirectional"))
      (node (ref "U$11") (pin "SDI") (pinfunction "SDI_SDI") (pintype "bidirectional"))
    )
    (net (code "24") (name "Net-(U$11-PadCKO)") (class "Default")
      (node (ref "U$11") (pin "CKO") (pinfunction "CKO_CKO") (pintype "bidirectional"))
      (node (ref "U$12") (pin "CKI") (pinfunction "CKI_CKI") (pintype "bidirectional"))
    )
    (net (code "25") (name "Net-(U$11-PadSDO)") (class "Default")
      (node (ref "U$11") (pin "SDO") (pinfunction "SDO_SDO") (pintype "bidirectional"))
      (node (ref "U$12") (pin "SDI") (pinfunction "SDI_SDI") (pintype "bidirectional"))
    )
    (net (code "26") (name "Net-(U$12-PadCKO)") (class "Default")
      (node (ref "U$12") (pin "CKO") (pinfunction "CKO_CKO") (pintype "bidirectional"))
      (node (ref "U$13") (pin "CKI") (pinfunction "CKI_CKI") (pintype "bidirectional"))
    )
    (net (code "27") (name "Net-(U$12-PadSDO)") (class "Default")
      (node (ref "U$12") (pin "SDO") (pinfunction "SDO_SDO") (pintype "bidirectional"))
      (node (ref "U$13") (pin "SDI") (pinfunction "SDI_SDI") (pintype "bidirectional"))
    )
    (net (code "28") (name "Net-(U$13-PadCKO)") (class "Default")
      (node (ref "U$13") (pin "CKO") (pinfunction "CKO_CKO") (pintype "bidirectional"))
      (node (ref "U$14") (pin "CKI") (pinfunction "CKI_CKI") (pintype "bidirectional"))
    )
    (net (code "29") (name "Net-(U$13-PadSDO)") (class "Default")
      (node (ref "U$13") (pin "SDO") (pinfunction "SDO_SDO") (pintype "bidirectional"))
      (node (ref "U$14") (pin "SDI") (pinfunction "SDI_SDI") (pintype "bidirectional"))
    )
    (net (code "30") (name "Net-(U$14-PadCKO)") (class "Default")
      (node (ref "U$14") (pin "CKO") (pinfunction "CKO_CKO") (pintype "bidirectional"))
      (node (ref "U$15") (pin "CKI") (pinfunction "CKI_CKI") (pintype "bidirectional"))
    )
    (net (code "31") (name "Net-(U$14-PadSDO)") (class "Default")
      (node (ref "U$14") (pin "SDO") (pinfunction "SDO_SDO") (pintype "bidirectional"))
      (node (ref "U$15") (pin "SDI") (pinfunction "SDI_SDI") (pintype "bidirectional"))
    )
    (net (code "32") (name "Net-(U$15-PadCKO)") (class "Default")
      (node (ref "U$15") (pin "CKO") (pinfunction "CKO_CKO") (pintype "bidirectional"))
      (node (ref "U$16") (pin "CKI") (pinfunction "CKI_CKI") (pintype "bidirectional"))
    )
    (net (code "33") (name "Net-(U$15-PadSDO)") (class "Default")
      (node (ref "U$15") (pin "SDO") (pinfunction "SDO_SDO") (pintype "bidirectional"))
      (node (ref "U$16") (pin "SDI") (pinfunction "SDI_SDI") (pintype "bidirectional"))
    )
    (net (code "34") (name "Net-(U$16-PadCKO)") (class "Default")
      (node (ref "U$16") (pin "CKO") (pinfunction "CKO_CKO") (pintype "bidirectional"))
      (node (ref "U$17") (pin "CKI") (pinfunction "CKI_CKI") (pintype "bidirectional"))
    )
    (net (code "35") (name "Net-(U$16-PadSDO)") (class "Default")
      (node (ref "U$16") (pin "SDO") (pinfunction "SDO_SDO") (pintype "bidirectional"))
      (node (ref "U$17") (pin "SDI") (pinfunction "SDI_SDI") (pintype "bidirectional"))
    )
    (net (code "36") (name "Net-(U$17-PadCKO)") (class "Default")
      (node (ref "U$17") (pin "CKO") (pinfunction "CKO_CKO") (pintype "bidirectional"))
      (node (ref "U$18") (pin "CKI") (pinfunction "CKI_CKI") (pintype "bidirectional"))
    )
    (net (code "37") (name "Net-(U$17-PadSDO)") (class "Default")
      (node (ref "U$17") (pin "SDO") (pinfunction "SDO_SDO") (pintype "bidirectional"))
      (node (ref "U$18") (pin "SDI") (pinfunction "SDI_SDI") (pintype "bidirectional"))
    )
    (net (code "38") (name "Net-(U$18-PadCKO)") (class "Default")
      (node (ref "U$18") (pin "CKO") (pinfunction "CKO_CKO") (pintype "bidirectional"))
      (node (ref "U$19") (pin "CKI") (pinfunction "CKI_CKI") (pintype "bidirectional"))
    )
    (net (code "39") (name "Net-(U$18-PadSDO)") (class "Default")
      (node (ref "U$18") (pin "SDO") (pinfunction "SDO_SDO") (pintype "bidirectional"))
      (node (ref "U$19") (pin "SDI") (pinfunction "SDI_SDI") (pintype "bidirectional"))
    )
    (net (code "40") (name "Net-(U$19-PadCKO)") (class "Default")
      (node (ref "U$19") (pin "CKO") (pinfunction "CKO_CKO") (pintype "bidirectional"))
      (node (ref "U$20") (pin "CKI") (pinfunction "CKI_CKI") (pintype "bidirectional"))
    )
    (net (code "41") (name "Net-(U$19-PadSDO)") (class "Default")
      (node (ref "U$19") (pin "SDO") (pinfunction "SDO_SDO") (pintype "bidirectional"))
      (node (ref "U$20") (pin "SDI") (pinfunction "SDI_SDI") (pintype "bidirectional"))
    )
    (net (code "42") (name "Net-(U$20-PadCKO)") (class "Default")
      (node (ref "U$20") (pin "CKO") (pinfunction "CKO_CKO") (pintype "bidirectional"))
      (node (ref "U$21") (pin "CKI") (pinfunction "CKI_CKI") (pintype "bidirectional"))
    )
    (net (code "43") (name "Net-(U$20-PadSDO)") (class "Default")
      (node (ref "U$20") (pin "SDO") (pinfunction "SDO_SDO") (pintype "bidirectional"))
      (node (ref "U$21") (pin "SDI") (pinfunction "SDI_SDI") (pintype "bidirectional"))
    )
    (net (code "44") (name "Net-(U$21-PadCKO)") (class "Default")
      (node (ref "U$21") (pin "CKO") (pinfunction "CKO_CKO") (pintype "bidirectional"))
      (node (ref "U$22") (pin "CKI") (pinfunction "CKI_CKI") (pintype "bidirectional"))
    )
    (net (code "45") (name "Net-(U$21-PadSDO)") (class "Default")
      (node (ref "U$21") (pin "SDO") (pinfunction "SDO_SDO") (pintype "bidirectional"))
      (node (ref "U$22") (pin "SDI") (pinfunction "SDI_SDI") (pintype "bidirectional"))
    )
    (net (code "46") (name "Net-(U$22-PadCKO)") (class "Default")
      (node (ref "U$22") (pin "CKO") (pinfunction "CKO_CKO") (pintype "bidirectional"))
      (node (ref "U$23") (pin "CKI") (pinfunction "CKI_CKI") (pintype "bidirectional"))
    )
    (net (code "47") (name "Net-(U$22-PadSDO)") (class "Default")
      (node (ref "U$22") (pin "SDO") (pinfunction "SDO_SDO") (pintype "bidirectional"))
      (node (ref "U$23") (pin "SDI") (pinfunction "SDI_SDI") (pintype "bidirectional"))
    )
    (net (code "48") (name "Net-(U$23-PadCKO)") (class "Default")
      (node (ref "U$23") (pin "CKO") (pinfunction "CKO_CKO") (pintype "bidirectional"))
      (node (ref "U$24") (pin "CKI") (pinfunction "CKI_CKI") (pintype "bidirectional"))
    )
    (net (code "49") (name "Net-(U$23-PadSDO)") (class "Default")
      (node (ref "U$23") (pin "SDO") (pinfunction "SDO_SDO") (pintype "bidirectional"))
      (node (ref "U$24") (pin "SDI") (pinfunction "SDI_SDI") (pintype "bidirectional"))
    )
    (net (code "50") (name "Net-(U$24-PadCKO)") (class "Default")
      (node (ref "U$24") (pin "CKO") (pinfunction "CKO_CKO") (pintype "bidirectional"))
      (node (ref "U$25") (pin "CKI") (pinfunction "CKI_CKI") (pintype "bidirectional"))
    )
    (net (code "51") (name "Net-(U$24-PadSDO)") (class "Default")
      (node (ref "U$24") (pin "SDO") (pinfunction "SDO_SDO") (pintype "bidirectional"))
      (node (ref "U$25") (pin "SDI") (pinfunction "SDI_SDI") (pintype "bidirectional"))
    )
    (net (code "52") (name "Net-(U$25-PadCKO)") (class "Default")
      (node (ref "U$25") (pin "CKO") (pinfunction "CKO_CKO") (pintype "bidirectional"))
      (node (ref "U$26") (pin "CKI") (pinfunction "CKI_CKI") (pintype "bidirectional"))
    )
    (net (code "53") (name "Net-(U$25-PadSDO)") (class "Default")
      (node (ref "U$25") (pin "SDO") (pinfunction "SDO_SDO") (pintype "bidirectional"))
      (node (ref "U$26") (pin "SDI") (pinfunction "SDI_SDI") (pintype "bidirectional"))
    )
    (net (code "54") (name "Net-(U$26-PadCKO)") (class "Default")
      (node (ref "U$26") (pin "CKO") (pinfunction "CKO_CKO") (pintype "bidirectional"))
      (node (ref "U$27") (pin "CKI") (pinfunction "CKI_CKI") (pintype "bidirectional"))
    )
    (net (code "55") (name "Net-(U$26-PadSDO)") (class "Default")
      (node (ref "U$26") (pin "SDO") (pinfunction "SDO_SDO") (pintype "bidirectional"))
      (node (ref "U$27") (pin "SDI") (pinfunction "SDI_SDI") (pintype "bidirectional"))
    )
    (net (code "56") (name "Net-(U$27-PadCKO)") (class "Default")
      (node (ref "U$27") (pin "CKO") (pinfunction "CKO_CKO") (pintype "bidirectional"))
      (node (ref "U$28") (pin "CKI") (pinfunction "CKI_CKI") (pintype "bidirectional"))
    )
    (net (code "57") (name "Net-(U$27-PadSDO)") (class "Default")
      (node (ref "U$27") (pin "SDO") (pinfunction "SDO_SDO") (pintype "bidirectional"))
      (node (ref "U$28") (pin "SDI") (pinfunction "SDI_SDI") (pintype "bidirectional"))
    )
    (net (code "58") (name "Net-(U$28-PadCKO)") (class "Default")
      (node (ref "U$28") (pin "CKO") (pinfunction "CKO_CKO") (pintype "bidirectional"))
      (node (ref "U$29") (pin "CKI") (pinfunction "CKI_CKI") (pintype "bidirectional"))
    )
    (net (code "59") (name "Net-(U$28-PadSDO)") (class "Default")
      (node (ref "U$28") (pin "SDO") (pinfunction "SDO_SDO") (pintype "bidirectional"))
      (node (ref "U$29") (pin "SDI") (pinfunction "SDI_SDI") (pintype "bidirectional"))
    )
    (net (code "60") (name "Net-(U$29-PadCKO)") (class "Default")
      (node (ref "U$29") (pin "CKO") (pinfunction "CKO_CKO") (pintype "bidirectional"))
      (node (ref "U$30") (pin "CKI") (pinfunction "CKI_CKI") (pintype "bidirectional"))
    )
    (net (code "61") (name "Net-(U$29-PadSDO)") (class "Default")
      (node (ref "U$29") (pin "SDO") (pinfunction "SDO_SDO") (pintype "bidirectional"))
      (node (ref "U$30") (pin "SDI") (pinfunction "SDI_SDI") (pintype "bidirectional"))
    )
    (net (code "62") (name "Net-(U$30-PadCKO)") (class "Default")
      (node (ref "U$30") (pin "CKO") (pinfunction "CKO_CKO") (pintype "bidirectional"))
      (node (ref "U$31") (pin "CKI") (pinfunction "CKI_CKI") (pintype "bidirectional"))
    )
    (net (code "63") (name "Net-(U$30-PadSDO)") (class "Default")
      (node (ref "U$30") (pin "SDO") (pinfunction "SDO_SDO") (pintype "bidirectional"))
      (node (ref "U$31") (pin "SDI") (pinfunction "SDI_SDI") (pintype "bidirectional"))
    )
    (net (code "64") (name "Net-(U$31-PadCKO)") (class "Default")
      (node (ref "U$31") (pin "CKO") (pinfunction "CKO_CKO") (pintype "bidirectional"))
      (node (ref "U$32") (pin "CKI") (pinfunction "CKI_CKI") (pintype "bidirectional"))
    )
    (net (code "65") (name "Net-(U$31-PadSDO)") (class "Default")
      (node (ref "U$31") (pin "SDO") (pinfunction "SDO_SDO") (pintype "bidirectional"))
      (node (ref "U$32") (pin "SDI") (pinfunction "SDI_SDI") (pintype "bidirectional"))
    )
    (net (code "66") (name "Net-(U$32-PadCKO)") (class "Default")
      (node (ref "U$32") (pin "CKO") (pinfunction "CKO_CKO") (pintype "bidirectional"))
      (node (ref "U$33") (pin "CKI") (pinfunction "CKI_CKI") (pintype "bidirectional"))
    )
    (net (code "67") (name "Net-(U$32-PadSDO)") (class "Default")
      (node (ref "U$32") (pin "SDO") (pinfunction "SDO_SDO") (pintype "bidirectional"))
      (node (ref "U$33") (pin "SDI") (pinfunction "SDI_SDI") (pintype "bidirectional"))
    )
    (net (code "68") (name "Net-(U$33-PadCKO)") (class "Default")
      (node (ref "U$33") (pin "CKO") (pinfunction "CKO_CKO") (pintype "bidirectional"))
      (node (ref "U$34") (pin "CKI") (pinfunction "CKI_CKI") (pintype "bidirectional"))
    )
    (net (code "69") (name "Net-(U$33-PadSDO)") (class "Default")
      (node (ref "U$33") (pin "SDO") (pinfunction "SDO_SDO") (pintype "bidirectional"))
      (node (ref "U$34") (pin "SDI") (pinfunction "SDI_SDI") (pintype "bidirectional"))
    )
    (net (code "70") (name "Net-(U$34-PadCKO)") (class "Default")
      (node (ref "U$34") (pin "CKO") (pinfunction "CKO_CKO") (pintype "bidirectional"))
      (node (ref "U$35") (pin "CKI") (pinfunction "CKI_CKI") (pintype "bidirectional"))
    )
    (net (code "71") (name "Net-(U$34-PadSDO)") (class "Default")
      (node (ref "U$34") (pin "SDO") (pinfunction "SDO_SDO") (pintype "bidirectional"))
      (node (ref "U$35") (pin "SDI") (pinfunction "SDI_SDI") (pintype "bidirectional"))
    )
    (net (code "72") (name "Net-(U$35-PadCKO)") (class "Default")
      (node (ref "U$35") (pin "CKO") (pinfunction "CKO_CKO") (pintype "bidirectional"))
      (node (ref "U$36") (pin "CKI") (pinfunction "CKI_CKI") (pintype "bidirectional"))
    )
    (net (code "73") (name "Net-(U$35-PadSDO)") (class "Default")
      (node (ref "U$35") (pin "SDO") (pinfunction "SDO_SDO") (pintype "bidirectional"))
      (node (ref "U$36") (pin "SDI") (pinfunction "SDI_SDI") (pintype "bidirectional"))
    )
    (net (code "74") (name "Net-(U$36-PadCKO)") (class "Default")
      (node (ref "U$36") (pin "CKO") (pinfunction "CKO_CKO") (pintype "bidirectional"))
      (node (ref "U$37") (pin "CKI") (pinfunction "CKI_CKI") (pintype "bidirectional"))
    )
    (net (code "75") (name "Net-(U$36-PadSDO)") (class "Default")
      (node (ref "U$36") (pin "SDO") (pinfunction "SDO_SDO") (pintype "bidirectional"))
      (node (ref "U$37") (pin "SDI") (pinfunction "SDI_SDI") (pintype "bidirectional"))
    )
    (net (code "76") (name "Net-(U$37-PadCKO)") (class "Default")
      (node (ref "U$37") (pin "CKO") (pinfunction "CKO_CKO") (pintype "bidirectional"))
      (node (ref "U$38") (pin "CKI") (pinfunction "CKI_CKI") (pintype "bidirectional"))
    )
    (net (code "77") (name "Net-(U$37-PadSDO)") (class "Default")
      (node (ref "U$37") (pin "SDO") (pinfunction "SDO_SDO") (pintype "bidirectional"))
      (node (ref "U$38") (pin "SDI") (pinfunction "SDI_SDI") (pintype "bidirectional"))
    )
    (net (code "78") (name "Net-(U$38-PadCKO)") (class "Default")
      (node (ref "U$38") (pin "CKO") (pinfunction "CKO_CKO") (pintype "bidirectional"))
      (node (ref "U$39") (pin "CKI") (pinfunction "CKI_CKI") (pintype "bidirectional"))
    )
    (net (code "79") (name "Net-(U$38-PadSDO)") (class "Default")
      (node (ref "U$38") (pin "SDO") (pinfunction "SDO_SDO") (pintype "bidirectional"))
      (node (ref "U$39") (pin "SDI") (pinfunction "SDI_SDI") (pintype "bidirectional"))
    )
    (net (code "80") (name "Net-(U$39-PadCKO)") (class "Default")
      (node (ref "U$39") (pin "CKO") (pinfunction "CKO_CKO") (pintype "bidirectional"))
      (node (ref "U$40") (pin "CKI") (pinfunction "CKI_CKI") (pintype "bidirectional"))
    )
    (net (code "81") (name "Net-(U$39-PadSDO)") (class "Default")
      (node (ref "U$39") (pin "SDO") (pinfunction "SDO_SDO") (pintype "bidirectional"))
      (node (ref "U$40") (pin "SDI") (pinfunction "SDI_SDI") (pintype "bidirectional"))
    )
    (net (code "82") (name "Net-(U$40-PadCKO)") (class "Default")
      (node (ref "U$40") (pin "CKO") (pinfunction "CKO_CKO") (pintype "bidirectional"))
      (node (ref "U$41") (pin "CKI") (pinfunction "CKI_CKI") (pintype "bidirectional"))
    )
    (net (code "83") (name "Net-(U$40-PadSDO)") (class "Default")
      (node (ref "U$40") (pin "SDO") (pinfunction "SDO_SDO") (pintype "bidirectional"))
      (node (ref "U$41") (pin "SDI") (pinfunction "SDI_SDI") (pintype "bidirectional"))
    )
    (net (code "84") (name "Net-(U$41-PadCKO)") (class "Default")
      (node (ref "U$41") (pin "CKO") (pinfunction "CKO_CKO") (pintype "bidirectional"))
      (node (ref "U$42") (pin "CKI") (pinfunction "CKI_CKI") (pintype "bidirectional"))
    )
    (net (code "85") (name "Net-(U$41-PadSDO)") (class "Default")
      (node (ref "U$41") (pin "SDO") (pinfunction "SDO_SDO") (pintype "bidirectional"))
      (node (ref "U$42") (pin "SDI") (pinfunction "SDI_SDI") (pintype "bidirectional"))
    )
    (net (code "86") (name "Net-(U$42-PadCKO)") (class "Default")
      (node (ref "U$42") (pin "CKO") (pinfunction "CKO_CKO") (pintype "bidirectional"))
      (node (ref "U$43") (pin "CKI") (pinfunction "CKI_CKI") (pintype "bidirectional"))
    )
    (net (code "87") (name "Net-(U$42-PadSDO)") (class "Default")
      (node (ref "U$42") (pin "SDO") (pinfunction "SDO_SDO") (pintype "bidirectional"))
      (node (ref "U$43") (pin "SDI") (pinfunction "SDI_SDI") (pintype "bidirectional"))
    )
    (net (code "88") (name "Net-(U$43-PadCKO)") (class "Default")
      (node (ref "U$43") (pin "CKO") (pinfunction "CKO_CKO") (pintype "bidirectional"))
      (node (ref "U$44") (pin "CKI") (pinfunction "CKI_CKI") (pintype "bidirectional"))
    )
    (net (code "89") (name "Net-(U$43-PadSDO)") (class "Default")
      (node (ref "U$43") (pin "SDO") (pinfunction "SDO_SDO") (pintype "bidirectional"))
      (node (ref "U$44") (pin "SDI") (pinfunction "SDI_SDI") (pintype "bidirectional"))
    )
    (net (code "90") (name "Net-(U$44-PadCKO)") (class "Default")
      (node (ref "U$44") (pin "CKO") (pinfunction "CKO_CKO") (pintype "bidirectional"))
      (node (ref "U$45") (pin "CKI") (pinfunction "CKI_CKI") (pintype "bidirectional"))
    )
    (net (code "91") (name "Net-(U$44-PadSDO)") (class "Default")
      (node (ref "U$44") (pin "SDO") (pinfunction "SDO_SDO") (pintype "bidirectional"))
      (node (ref "U$45") (pin "SDI") (pinfunction "SDI_SDI") (pintype "bidirectional"))
    )
    (net (code "92") (name "Net-(U$45-PadCKO)") (class "Default")
      (node (ref "U$45") (pin "CKO") (pinfunction "CKO_CKO") (pintype "bidirectional"))
      (node (ref "U$46") (pin "CKI") (pinfunction "CKI_CKI") (pintype "bidirectional"))
    )
    (net (code "93") (name "Net-(U$45-PadSDO)") (class "Default")
      (node (ref "U$45") (pin "SDO") (pinfunction "SDO_SDO") (pintype "bidirectional"))
      (node (ref "U$46") (pin "SDI") (pinfunction "SDI_SDI") (pintype "bidirectional"))
    )
    (net (code "94") (name "Net-(U$46-PadCKO)") (class "Default")
      (node (ref "U$46") (pin "CKO") (pinfunction "CKO_CKO") (pintype "bidirectional"))
      (node (ref "U$47") (pin "CKI") (pinfunction "CKI_CKI") (pintype "bidirectional"))
    )
    (net (code "95") (name "Net-(U$46-PadSDO)") (class "Default")
      (node (ref "U$46") (pin "SDO") (pinfunction "SDO_SDO") (pintype "bidirectional"))
      (node (ref "U$47") (pin "SDI") (pinfunction "SDI_SDI") (pintype "bidirectional"))
    )
    (net (code "96") (name "Net-(U$47-PadCKO)") (class "Default")
      (node (ref "U$47") (pin "CKO") (pinfunction "CKO_CKO") (pintype "bidirectional"))
      (node (ref "U$48") (pin "CKI") (pinfunction "CKI_CKI") (pintype "bidirectional"))
    )
    (net (code "97") (name "Net-(U$47-PadSDO)") (class "Default")
      (node (ref "U$47") (pin "SDO") (pinfunction "SDO_SDO") (pintype "bidirectional"))
      (node (ref "U$48") (pin "SDI") (pinfunction "SDI_SDI") (pintype "bidirectional"))
    )
    (net (code "98") (name "Net-(U$48-PadCKO)") (class "Default")
      (node (ref "U$48") (pin "CKO") (pinfunction "CKO_CKO") (pintype "bidirectional"))
      (node (ref "U$49") (pin "CKI") (pinfunction "CKI_CKI") (pintype "bidirectional"))
    )
    (net (code "99") (name "Net-(U$48-PadSDO)") (class "Default")
      (node (ref "U$48") (pin "SDO") (pinfunction "SDO_SDO") (pintype "bidirectional"))
      (node (ref "U$49") (pin "SDI") (pinfunction "SDI_SDI") (pintype "bidirectional"))
    )
    (net (code "100") (name "Net-(U$49-PadCKO)") (class "Default")
      (node (ref "U$49") (pin "CKO") (pinfunction "CKO_CKO") (pintype "bidirectional"))
      (node (ref "U$50") (pin "CKI") (pinfunction "CKI_CKI") (pintype "bidirectional"))
    )
    (net (code "101") (name "Net-(U$49-PadSDO)") (class "Default")
      (node (ref "U$49") (pin "SDO") (pinfunction "SDO_SDO") (pintype "bidirectional"))
      (node (ref "U$50") (pin "SDI") (pinfunction "SDI_SDI") (pintype "bidirectional"))
    )
    (net (code "102") (name "Net-(U$50-PadCKO)") (class "Default")
      (node (ref "U$50") (pin "CKO") (pinfunction "CKO_CKO") (pintype "bidirectional"))
      (node (ref "U$51") (pin "CKI") (pinfunction "CKI_CKI") (pintype "bidirectional"))
    )
    (net (code "103") (name "Net-(U$50-PadSDO)") (class "Default")
      (node (ref "U$50") (pin "SDO") (pinfunction "SDO_SDO") (pintype "bidirectional"))
      (node (ref "U$51") (pin "SDI") (pinfunction "SDI_SDI") (pintype "bidirectional"))
    )
    (net (code "104") (name "Net-(U$51-PadCKO)") (class "Default")
      (node (ref "U$51") (pin "CKO") (pinfunction "CKO_CKO") (pintype "bidirectional"))
      (node (ref "U$52") (pin "CKI") (pinfunction "CKI_CKI") (pintype "bidirectional"))
    )
    (net (code "105") (name "Net-(U$51-PadSDO)") (class "Default")
      (node (ref "U$51") (pin "SDO") (pinfunction "SDO_SDO") (pintype "bidirectional"))
      (node (ref "U$52") (pin "SDI") (pinfunction "SDI_SDI") (pintype "bidirectional"))
    )
    (net (code "106") (name "Net-(U$52-PadCKO)") (class "Default")
      (node (ref "U$52") (pin "CKO") (pinfunction "CKO_CKO") (pintype "bidirectional"))
      (node (ref "U$53") (pin "CKI") (pinfunction "CKI_CKI") (pintype "bidirectional"))
    )
    (net (code "107") (name "Net-(U$52-PadSDO)") (class "Default")
      (node (ref "U$52") (pin "SDO") (pinfunction "SDO_SDO") (pintype "bidirectional"))
      (node (ref "U$53") (pin "SDI") (pinfunction "SDI_SDI") (pintype "bidirectional"))
    )
    (net (code "108") (name "Net-(U$53-PadCKO)") (class "Default")
      (node (ref "U$53") (pin "CKO") (pinfunction "CKO_CKO") (pintype "bidirectional"))
      (node (ref "U$54") (pin "CKI") (pinfunction "CKI_CKI") (pintype "bidirectional"))
    )
    (net (code "109") (name "Net-(U$53-PadSDO)") (class "Default")
      (node (ref "U$53") (pin "SDO") (pinfunction "SDO_SDO") (pintype "bidirectional"))
      (node (ref "U$54") (pin "SDI") (pinfunction "SDI_SDI") (pintype "bidirectional"))
    )
    (net (code "110") (name "Net-(U$54-PadCKO)") (class "Default")
      (node (ref "U$54") (pin "CKO") (pinfunction "CKO_CKO") (pintype "bidirectional"))
      (node (ref "U$55") (pin "CKI") (pinfunction "CKI_CKI") (pintype "bidirectional"))
    )
    (net (code "111") (name "Net-(U$54-PadSDO)") (class "Default")
      (node (ref "U$54") (pin "SDO") (pinfunction "SDO_SDO") (pintype "bidirectional"))
      (node (ref "U$55") (pin "SDI") (pinfunction "SDI_SDI") (pintype "bidirectional"))
    )
    (net (code "112") (name "Net-(U$55-PadCKO)") (class "Default")
      (node (ref "U$55") (pin "CKO") (pinfunction "CKO_CKO") (pintype "bidirectional"))
      (node (ref "U$56") (pin "CKI") (pinfunction "CKI_CKI") (pintype "bidirectional"))
    )
    (net (code "113") (name "Net-(U$55-PadSDO)") (class "Default")
      (node (ref "U$55") (pin "SDO") (pinfunction "SDO_SDO") (pintype "bidirectional"))
      (node (ref "U$56") (pin "SDI") (pinfunction "SDI_SDI") (pintype "bidirectional"))
    )
    (net (code "114") (name "Net-(U$56-PadCKO)") (class "Default")
      (node (ref "U$56") (pin "CKO") (pinfunction "CKO_CKO") (pintype "bidirectional"))
      (node (ref "U$57") (pin "CKI") (pinfunction "CKI_CKI") (pintype "bidirectional"))
    )
    (net (code "115") (name "Net-(U$56-PadSDO)") (class "Default")
      (node (ref "U$56") (pin "SDO") (pinfunction "SDO_SDO") (pintype "bidirectional"))
      (node (ref "U$57") (pin "SDI") (pinfunction "SDI_SDI") (pintype "bidirectional"))
    )
    (net (code "116") (name "Net-(U$57-PadCKO)") (class "Default")
      (node (ref "U$57") (pin "CKO") (pinfunction "CKO_CKO") (pintype "bidirectional"))
      (node (ref "U$58") (pin "CKI") (pinfunction "CKI_CKI") (pintype "bidirectional"))
    )
    (net (code "117") (name "Net-(U$57-PadSDO)") (class "Default")
      (node (ref "U$57") (pin "SDO") (pinfunction "SDO_SDO") (pintype "bidirectional"))
      (node (ref "U$58") (pin "SDI") (pinfunction "SDI_SDI") (pintype "bidirectional"))
    )
    (net (code "118") (name "Net-(U$58-PadCKO)") (class "Default")
      (node (ref "U$58") (pin "CKO") (pinfunction "CKO_CKO") (pintype "bidirectional"))
      (node (ref "U$59") (pin "CKI") (pinfunction "CKI_CKI") (pintype "bidirectional"))
    )
    (net (code "119") (name "Net-(U$58-PadSDO)") (class "Default")
      (node (ref "U$58") (pin "SDO") (pinfunction "SDO_SDO") (pintype "bidirectional"))
      (node (ref "U$59") (pin "SDI") (pinfunction "SDI_SDI") (pintype "bidirectional"))
    )
    (net (code "120") (name "Net-(U$59-PadCKO)") (class "Default")
      (node (ref "U$59") (pin "CKO") (pinfunction "CKO_CKO") (pintype "bidirectional"))
      (node (ref "U$60") (pin "CKI") (pinfunction "CKI_CKI") (pintype "bidirectional"))
    )
    (net (code "121") (name "Net-(U$59-PadSDO)") (class "Default")
      (node (ref "U$59") (pin "SDO") (pinfunction "SDO_SDO") (pintype "bidirectional"))
      (node (ref "U$60") (pin "SDI") (pinfunction "SDI_SDI") (pintype "bidirectional"))
    )
    (net (code "122") (name "Net-(U$60-PadCKO)") (class "Default")
      (node (ref "U$60") (pin "CKO") (pinfunction "CKO_CKO") (pintype "bidirectional"))
      (node (ref "U$61") (pin "CKI") (pinfunction "CKI_CKI") (pintype "bidirectional"))
    )
    (net (code "123") (name "Net-(U$60-PadSDO)") (class "Default")
      (node (ref "U$60") (pin "SDO") (pinfunction "SDO_SDO") (pintype "bidirectional"))
      (node (ref "U$61") (pin "SDI") (pinfunction "SDI_SDI") (pintype "bidirectional"))
    )
    (net (code "124") (name "Net-(U$61-PadCKO)") (class "Default")
      (node (ref "U$61") (pin "CKO") (pinfunction "CKO_CKO") (pintype "bidirectional"))
      (node (ref "U$62") (pin "CKI") (pinfunction "CKI_CKI") (pintype "bidirectional"))
    )
    (net (code "125") (name "Net-(U$61-PadSDO)") (class "Default")
      (node (ref "U$61") (pin "SDO") (pinfunction "SDO_SDO") (pintype "bidirectional"))
      (node (ref "U$62") (pin "SDI") (pinfunction "SDI_SDI") (pintype "bidirectional"))
    )
    (net (code "126") (name "Net-(U$62-PadCKO)") (class "Default")
      (node (ref "U$62") (pin "CKO") (pinfunction "CKO_CKO") (pintype "bidirectional"))
      (node (ref "U$63") (pin "CKI") (pinfunction "CKI_CKI") (pintype "bidirectional"))
    )
    (net (code "127") (name "Net-(U$62-PadSDO)") (class "Default")
      (node (ref "U$62") (pin "SDO") (pinfunction "SDO_SDO") (pintype "bidirectional"))
      (node (ref "U$63") (pin "SDI") (pinfunction "SDI_SDI") (pintype "bidirectional"))
    )
    (net (code "128") (name "Net-(U$63-PadCKO)") (class "Default")
      (node (ref "U$63") (pin "CKO") (pinfunction "CKO_CKO") (pintype "bidirectional"))
      (node (ref "U$64") (pin "CKI") (pinfunction "CKI_CKI") (pintype "bidirectional"))
    )
    (net (code "129") (name "Net-(U$63-PadSDO)") (class "Default")
      (node (ref "U$63") (pin "SDO") (pinfunction "SDO_SDO") (pintype "bidirectional"))
      (node (ref "U$64") (pin "SDI") (pinfunction "SDI_SDI") (pintype "bidirectional"))
    )
    (net (code "130") (name "Net-(U$64-PadCKO)") (class "Default")
      (node (ref "U$64") (pin "CKO") (pinfunction "CKO_CKO") (pintype "bidirectional"))
      (node (ref "U$65") (pin "CKI") (pinfunction "CKI_CKI") (pintype "bidirectional"))
    )
    (net (code "131") (name "Net-(U$64-PadSDO)") (class "Default")
      (node (ref "U$64") (pin "SDO") (pinfunction "SDO_SDO") (pintype "bidirectional"))
      (node (ref "U$65") (pin "SDI") (pinfunction "SDI_SDI") (pintype "bidirectional"))
    )
    (net (code "132") (name "Net-(U$65-PadCKO)") (class "Default")
      (node (ref "U$65") (pin "CKO") (pinfunction "CKO_CKO") (pintype "bidirectional"))
      (node (ref "U$66") (pin "CKI") (pinfunction "CKI_CKI") (pintype "bidirectional"))
    )
    (net (code "133") (name "Net-(U$65-PadSDO)") (class "Default")
      (node (ref "U$65") (pin "SDO") (pinfunction "SDO_SDO") (pintype "bidirectional"))
      (node (ref "U$66") (pin "SDI") (pinfunction "SDI_SDI") (pintype "bidirectional"))
    )
    (net (code "134") (name "Net-(U$66-PadCKO)") (class "Default")
      (node (ref "U$66") (pin "CKO") (pinfunction "CKO_CKO") (pintype "bidirectional"))
      (node (ref "U$67") (pin "CKI") (pinfunction "CKI_CKI") (pintype "bidirectional"))
    )
    (net (code "135") (name "Net-(U$66-PadSDO)") (class "Default")
      (node (ref "U$66") (pin "SDO") (pinfunction "SDO_SDO") (pintype "bidirectional"))
      (node (ref "U$67") (pin "SDI") (pinfunction "SDI_SDI") (pintype "bidirectional"))
    )
    (net (code "136") (name "Net-(U$67-PadCKO)") (class "Default")
      (node (ref "U$67") (pin "CKO") (pinfunction "CKO_CKO") (pintype "bidirectional"))
      (node (ref "U$68") (pin "CKI") (pinfunction "CKI_CKI") (pintype "bidirectional"))
    )
    (net (code "137") (name "Net-(U$67-PadSDO)") (class "Default")
      (node (ref "U$67") (pin "SDO") (pinfunction "SDO_SDO") (pintype "bidirectional"))
      (node (ref "U$68") (pin "SDI") (pinfunction "SDI_SDI") (pintype "bidirectional"))
    )
    (net (code "138") (name "Net-(U$68-PadCKO)") (class "Default")
      (node (ref "U$68") (pin "CKO") (pinfunction "CKO_CKO") (pintype "bidirectional"))
      (node (ref "U$69") (pin "CKI") (pinfunction "CKI_CKI") (pintype "bidirectional"))
    )
    (net (code "139") (name "Net-(U$68-PadSDO)") (class "Default")
      (node (ref "U$68") (pin "SDO") (pinfunction "SDO_SDO") (pintype "bidirectional"))
      (node (ref "U$69") (pin "SDI") (pinfunction "SDI_SDI") (pintype "bidirectional"))
    )
    (net (code "140") (name "Net-(U$69-PadCKO)") (class "Default")
      (node (ref "U$69") (pin "CKO") (pinfunction "CKO_CKO") (pintype "bidirectional"))
      (node (ref "U$70") (pin "CKI") (pinfunction "CKI_CKI") (pintype "bidirectional"))
    )
    (net (code "141") (name "Net-(U$69-PadSDO)") (class "Default")
      (node (ref "U$69") (pin "SDO") (pinfunction "SDO_SDO") (pintype "bidirectional"))
      (node (ref "U$70") (pin "SDI") (pinfunction "SDI_SDI") (pintype "bidirectional"))
    )
    (net (code "142") (name "Net-(U$70-PadCKO)") (class "Default")
      (node (ref "U$70") (pin "CKO") (pinfunction "CKO_CKO") (pintype "bidirectional"))
      (node (ref "U$71") (pin "CKI") (pinfunction "CKI_CKI") (pintype "bidirectional"))
    )
    (net (code "143") (name "Net-(U$70-PadSDO)") (class "Default")
      (node (ref "U$70") (pin "SDO") (pinfunction "SDO_SDO") (pintype "bidirectional"))
      (node (ref "U$71") (pin "SDI") (pinfunction "SDI_SDI") (pintype "bidirectional"))
    )
    (net (code "144") (name "Net-(U$71-PadCKO)") (class "Default")
      (node (ref "U$71") (pin "CKO") (pinfunction "CKO_CKO") (pintype "bidirectional"))
      (node (ref "U$72") (pin "CKI") (pinfunction "CKI_CKI") (pintype "bidirectional"))
    )
    (net (code "145") (name "Net-(U$71-PadSDO)") (class "Default")
      (node (ref "U$71") (pin "SDO") (pinfunction "SDO_SDO") (pintype "bidirectional"))
      (node (ref "U$72") (pin "SDI") (pinfunction "SDI_SDI") (pintype "bidirectional"))
    )
    (net (code "146") (name "Net-(U$72-PadCKO)") (class "Default")
      (node (ref "U$72") (pin "CKO") (pinfunction "CKO_CKO") (pintype "bidirectional"))
      (node (ref "U$73") (pin "CKI") (pinfunction "CKI_CKI") (pintype "bidirectional"))
    )
    (net (code "147") (name "Net-(U$72-PadSDO)") (class "Default")
      (node (ref "U$72") (pin "SDO") (pinfunction "SDO_SDO") (pintype "bidirectional"))
      (node (ref "U$73") (pin "SDI") (pinfunction "SDI_SDI") (pintype "bidirectional"))
    )
    (net (code "148") (name "Net-(U$73-PadCKO)") (class "Default")
      (node (ref "U$73") (pin "CKO") (pinfunction "CKO_CKO") (pintype "bidirectional"))
      (node (ref "U$74") (pin "CKI") (pinfunction "CKI_CKI") (pintype "bidirectional"))
    )
    (net (code "149") (name "Net-(U$73-PadSDO)") (class "Default")
      (node (ref "U$73") (pin "SDO") (pinfunction "SDO_SDO") (pintype "bidirectional"))
      (node (ref "U$74") (pin "SDI") (pinfunction "SDI_SDI") (pintype "bidirectional"))
    )
    (net (code "150") (name "Net-(U$74-PadCKO)") (class "Default")
      (node (ref "U$74") (pin "CKO") (pinfunction "CKO_CKO") (pintype "bidirectional"))
      (node (ref "U$75") (pin "CKI") (pinfunction "CKI_CKI") (pintype "bidirectional"))
    )
    (net (code "151") (name "Net-(U$74-PadSDO)") (class "Default")
      (node (ref "U$74") (pin "SDO") (pinfunction "SDO_SDO") (pintype "bidirectional"))
      (node (ref "U$75") (pin "SDI") (pinfunction "SDI_SDI") (pintype "bidirectional"))
    )
    (net (code "152") (name "Net-(U$75-PadCKO)") (class "Default")
      (node (ref "U$75") (pin "CKO") (pinfunction "CKO_CKO") (pintype "bidirectional"))
      (node (ref "U$76") (pin "CKI") (pinfunction "CKI_CKI") (pintype "bidirectional"))
    )
    (net (code "153") (name "Net-(U$75-PadSDO)") (class "Default")
      (node (ref "U$75") (pin "SDO") (pinfunction "SDO_SDO") (pintype "bidirectional"))
      (node (ref "U$76") (pin "SDI") (pinfunction "SDI_SDI") (pintype "bidirectional"))
    )
    (net (code "154") (name "Net-(U$76-PadCKO)") (class "Default")
      (node (ref "U$76") (pin "CKO") (pinfunction "CKO_CKO") (pintype "bidirectional"))
      (node (ref "U$77") (pin "CKI") (pinfunction "CKI_CKI") (pintype "bidirectional"))
    )
    (net (code "155") (name "Net-(U$76-PadSDO)") (class "Default")
      (node (ref "U$76") (pin "SDO") (pinfunction "SDO_SDO") (pintype "bidirectional"))
      (node (ref "U$77") (pin "SDI") (pinfunction "SDI_SDI") (pintype "bidirectional"))
    )
    (net (code "156") (name "Net-(U$77-PadCKO)") (class "Default")
      (node (ref "U$77") (pin "CKO") (pinfunction "CKO_CKO") (pintype "bidirectional"))
      (node (ref "U$78") (pin "CKI") (pinfunction "CKI_CKI") (pintype "bidirectional"))
    )
    (net (code "157") (name "Net-(U$77-PadSDO)") (class "Default")
      (node (ref "U$77") (pin "SDO") (pinfunction "SDO_SDO") (pintype "bidirectional"))
      (node (ref "U$78") (pin "SDI") (pinfunction "SDI_SDI") (pintype "bidirectional"))
    )
    (net (code "158") (name "Net-(U$78-PadCKO)") (class "Default")
      (node (ref "U$78") (pin "CKO") (pinfunction "CKO_CKO") (pintype "bidirectional"))
      (node (ref "U$79") (pin "CKI") (pinfunction "CKI_CKI") (pintype "bidirectional"))
    )
    (net (code "159") (name "Net-(U$78-PadSDO)") (class "Default")
      (node (ref "U$78") (pin "SDO") (pinfunction "SDO_SDO") (pintype "bidirectional"))
      (node (ref "U$79") (pin "SDI") (pinfunction "SDI_SDI") (pintype "bidirectional"))
    )
    (net (code "160") (name "Net-(U$79-PadCKO)") (class "Default")
      (node (ref "U$79") (pin "CKO") (pinfunction "CKO_CKO") (pintype "bidirectional"))
      (node (ref "U$80") (pin "CKI") (pinfunction "CKI_CKI") (pintype "bidirectional"))
    )
    (net (code "161") (name "Net-(U$79-PadSDO)") (class "Default")
      (node (ref "U$79") (pin "SDO") (pinfunction "SDO_SDO") (pintype "bidirectional"))
      (node (ref "U$80") (pin "SDI") (pinfunction "SDI_SDI") (pintype "bidirectional"))
    )
    (net (code "162") (name "Net-(U$80-PadCKO)") (class "Default")
      (node (ref "U$80") (pin "CKO") (pinfunction "CKO_CKO") (pintype "bidirectional"))
      (node (ref "U$81") (pin "CKI") (pinfunction "CKI_CKI") (pintype "bidirectional"))
    )
    (net (code "163") (name "Net-(U$80-PadSDO)") (class "Default")
      (node (ref "U$80") (pin "SDO") (pinfunction "SDO_SDO") (pintype "bidirectional"))
      (node (ref "U$81") (pin "SDI") (pinfunction "SDI_SDI") (pintype "bidirectional"))
    )
    (net (code "164") (name "Net-(U$81-PadCKO)") (class "Default")
      (node (ref "U$81") (pin "CKO") (pinfunction "CKO_CKO") (pintype "bidirectional"))
      (node (ref "U$82") (pin "CKI") (pinfunction "CKI_CKI") (pintype "bidirectional"))
    )
    (net (code "165") (name "Net-(U$81-PadSDO)") (class "Default")
      (node (ref "U$81") (pin "SDO") (pinfunction "SDO_SDO") (pintype "bidirectional"))
      (node (ref "U$82") (pin "SDI") (pinfunction "SDI_SDI") (pintype "bidirectional"))
    )
    (net (code "166") (name "Net-(U$82-PadCKO)") (class "Default")
      (node (ref "U$82") (pin "CKO") (pinfunction "CKO_CKO") (pintype "bidirectional"))
      (node (ref "U$83") (pin "CKI") (pinfunction "CKI_CKI") (pintype "bidirectional"))
    )
    (net (code "167") (name "Net-(U$82-PadSDO)") (class "Default")
      (node (ref "U$82") (pin "SDO") (pinfunction "SDO_SDO") (pintype "bidirectional"))
      (node (ref "U$83") (pin "SDI") (pinfunction "SDI_SDI") (pintype "bidirectional"))
    )
    (net (code "168") (name "Net-(U$83-PadCKO)") (class "Default")
      (node (ref "U$83") (pin "CKO") (pinfunction "CKO_CKO") (pintype "bidirectional"))
      (node (ref "U$84") (pin "CKI") (pinfunction "CKI_CKI") (pintype "bidirectional"))
    )
    (net (code "169") (name "Net-(U$83-PadSDO)") (class "Default")
      (node (ref "U$83") (pin "SDO") (pinfunction "SDO_SDO") (pintype "bidirectional"))
      (node (ref "U$84") (pin "SDI") (pinfunction "SDI_SDI") (pintype "bidirectional"))
    )
    (net (code "170") (name "Net-(U$84-PadCKO)") (class "Default")
      (node (ref "U$84") (pin "CKO") (pinfunction "CKO_CKO") (pintype "bidirectional"))
      (node (ref "U$85") (pin "CKI") (pinfunction "CKI_CKI") (pintype "bidirectional"))
    )
    (net (code "171") (name "Net-(U$84-PadSDO)") (class "Default")
      (node (ref "U$84") (pin "SDO") (pinfunction "SDO_SDO") (pintype "bidirectional"))
      (node (ref "U$85") (pin "SDI") (pinfunction "SDI_SDI") (pintype "bidirectional"))
    )
    (net (code "172") (name "Net-(U$85-PadCKO)") (class "Default")
      (node (ref "U$85") (pin "CKO") (pinfunction "CKO_CKO") (pintype "bidirectional"))
      (node (ref "U$86") (pin "CKI") (pinfunction "CKI_CKI") (pintype "bidirectional"))
    )
    (net (code "173") (name "Net-(U$85-PadSDO)") (class "Default")
      (node (ref "U$85") (pin "SDO") (pinfunction "SDO_SDO") (pintype "bidirectional"))
      (node (ref "U$86") (pin "SDI") (pinfunction "SDI_SDI") (pintype "bidirectional"))
    )
    (net (code "174") (name "Net-(U$86-PadCKO)") (class "Default")
      (node (ref "U$86") (pin "CKO") (pinfunction "CKO_CKO") (pintype "bidirectional"))
      (node (ref "U$87") (pin "CKI") (pinfunction "CKI_CKI") (pintype "bidirectional"))
    )
    (net (code "175") (name "Net-(U$86-PadSDO)") (class "Default")
      (node (ref "U$86") (pin "SDO") (pinfunction "SDO_SDO") (pintype "bidirectional"))
      (node (ref "U$87") (pin "SDI") (pinfunction "SDI_SDI") (pintype "bidirectional"))
    )
    (net (code "176") (name "Net-(U$87-PadCKO)") (class "Default")
      (node (ref "U$87") (pin "CKO") (pinfunction "CKO_CKO") (pintype "bidirectional"))
      (node (ref "U$88") (pin "CKI") (pinfunction "CKI_CKI") (pintype "bidirectional"))
    )
    (net (code "177") (name "Net-(U$87-PadSDO)") (class "Default")
      (node (ref "U$87") (pin "SDO") (pinfunction "SDO_SDO") (pintype "bidirectional"))
      (node (ref "U$88") (pin "SDI") (pinfunction "SDI_SDI") (pintype "bidirectional"))
    )
    (net (code "178") (name "Net-(U$88-PadCKO)") (class "Default")
      (node (ref "U$88") (pin "CKO") (pinfunction "CKO_CKO") (pintype "bidirectional"))
      (node (ref "U$89") (pin "CKI") (pinfunction "CKI_CKI") (pintype "bidirectional"))
    )
    (net (code "179") (name "Net-(U$88-PadSDO)") (class "Default")
      (node (ref "U$88") (pin "SDO") (pinfunction "SDO_SDO") (pintype "bidirectional"))
      (node (ref "U$89") (pin "SDI") (pinfunction "SDI_SDI") (pintype "bidirectional"))
    )
    (net (code "180") (name "Net-(U$89-PadCKO)") (class "Default")
      (node (ref "U$89") (pin "CKO") (pinfunction "CKO_CKO") (pintype "bidirectional"))
      (node (ref "U$90") (pin "CKI") (pinfunction "CKI_CKI") (pintype "bidirectional"))
    )
    (net (code "181") (name "Net-(U$89-PadSDO)") (class "Default")
      (node (ref "U$89") (pin "SDO") (pinfunction "SDO_SDO") (pintype "bidirectional"))
      (node (ref "U$90") (pin "SDI") (pinfunction "SDI_SDI") (pintype "bidirectional"))
    )
    (net (code "182") (name "Net-(U$90-PadCKO)") (class "Default")
      (node (ref "U$90") (pin "CKO") (pinfunction "CKO_CKO") (pintype "bidirectional"))
      (node (ref "U$91") (pin "CKI") (pinfunction "CKI_CKI") (pintype "bidirectional"))
    )
    (net (code "183") (name "Net-(U$90-PadSDO)") (class "Default")
      (node (ref "U$90") (pin "SDO") (pinfunction "SDO_SDO") (pintype "bidirectional"))
      (node (ref "U$91") (pin "SDI") (pinfunction "SDI_SDI") (pintype "bidirectional"))
    )
    (net (code "184") (name "Net-(U$91-PadCKO)") (class "Default")
      (node (ref "U$91") (pin "CKO") (pinfunction "CKO_CKO") (pintype "bidirectional"))
      (node (ref "U$92") (pin "CKI") (pinfunction "CKI_CKI") (pintype "bidirectional"))
    )
    (net (code "185") (name "Net-(U$91-PadSDO)") (class "Default")
      (node (ref "U$91") (pin "SDO") (pinfunction "SDO_SDO") (pintype "bidirectional"))
      (node (ref "U$92") (pin "SDI") (pinfunction "SDI_SDI") (pintype "bidirectional"))
    )
    (net (code "186") (name "Net-(U$92-PadCKO)") (class "Default")
      (node (ref "U$92") (pin "CKO") (pinfunction "CKO_CKO") (pintype "bidirectional"))
      (node (ref "U$93") (pin "CKI") (pinfunction "CKI_CKI") (pintype "bidirectional"))
    )
    (net (code "187") (name "Net-(U$92-PadSDO)") (class "Default")
      (node (ref "U$92") (pin "SDO") (pinfunction "SDO_SDO") (pintype "bidirectional"))
      (node (ref "U$93") (pin "SDI") (pinfunction "SDI_SDI") (pintype "bidirectional"))
    )
    (net (code "188") (name "Net-(U$93-PadCKO)") (class "Default")
      (node (ref "U$93") (pin "CKO") (pinfunction "CKO_CKO") (pintype "bidirectional"))
      (node (ref "U$94") (pin "CKI") (pinfunction "CKI_CKI") (pintype "bidirectional"))
    )
    (net (code "189") (name "Net-(U$93-PadSDO)") (class "Default")
      (node (ref "U$93") (pin "SDO") (pinfunction "SDO_SDO") (pintype "bidirectional"))
      (node (ref "U$94") (pin "SDI") (pinfunction "SDI_SDI") (pintype "bidirectional"))
    )
    (net (code "190") (name "Net-(U$94-PadCKO)") (class "Default")
      (node (ref "U$94") (pin "CKO") (pinfunction "CKO_CKO") (pintype "bidirectional"))
      (node (ref "U$95") (pin "CKI") (pinfunction "CKI_CKI") (pintype "bidirectional"))
    )
    (net (code "191") (name "Net-(U$94-PadSDO)") (class "Default")
      (node (ref "U$94") (pin "SDO") (pinfunction "SDO_SDO") (pintype "bidirectional"))
      (node (ref "U$95") (pin "SDI") (pinfunction "SDI_SDI") (pintype "bidirectional"))
    )
    (net (code "192") (name "Net-(U$95-PadCKO)") (class "Default")
      (node (ref "U$95") (pin "CKO") (pinfunction "CKO_CKO") (pintype "bidirectional"))
      (node (ref "U$96") (pin "CKI") (pinfunction "CKI_CKI") (pintype "bidirectional"))
    )
    (net (code "193") (name "Net-(U$95-PadSDO)") (class "Default")
      (node (ref "U$95") (pin "SDO") (pinfunction "SDO_SDO") (pintype "bidirectional"))
      (node (ref "U$96") (pin "SDI") (pinfunction "SDI_SDI") (pintype "bidirectional"))
    )
    (net (code "194") (name "Net-(U$96-PadCKO)") (class "Default")
      (node (ref "U$96") (pin "CKO") (pinfunction "CKO_CKO") (pintype "bidirectional"))
      (node (ref "U$97") (pin "CKI") (pinfunction "CKI_CKI") (pintype "bidirectional"))
    )
    (net (code "195") (name "Net-(U$96-PadSDO)") (class "Default")
      (node (ref "U$96") (pin "SDO") (pinfunction "SDO_SDO") (pintype "bidirectional"))
      (node (ref "U$97") (pin "SDI") (pinfunction "SDI_SDI") (pintype "bidirectional"))
    )
    (net (code "196") (name "Net-(U$97-PadCKO)") (class "Default")
      (node (ref "U$97") (pin "CKO") (pinfunction "CKO_CKO") (pintype "bidirectional"))
      (node (ref "U$98") (pin "CKI") (pinfunction "CKI_CKI") (pintype "bidirectional"))
    )
    (net (code "197") (name "Net-(U$97-PadSDO)") (class "Default")
      (node (ref "U$97") (pin "SDO") (pinfunction "SDO_SDO") (pintype "bidirectional"))
      (node (ref "U$98") (pin "SDI") (pinfunction "SDI_SDI") (pintype "bidirectional"))
    )
    (net (code "198") (name "Net-(U$98-PadCKO)") (class "Default")
      (node (ref "U$98") (pin "CKO") (pinfunction "CKO_CKO") (pintype "bidirectional"))
      (node (ref "U$99") (pin "CKI") (pinfunction "CKI_CKI") (pintype "bidirectional"))
    )
    (net (code "199") (name "Net-(U$98-PadSDO)") (class "Default")
      (node (ref "U$98") (pin "SDO") (pinfunction "SDO_SDO") (pintype "bidirectional"))
      (node (ref "U$99") (pin "SDI") (pinfunction "SDI_SDI") (pintype "bidirectional"))
    )
    (net (code "200") (name "Net-(U$100-PadCKI)") (class "Default")
      (node (ref "U$100") (pin "CKI") (pinfunction "CKI_CKI") (pintype "bidirectional"))
      (node (ref "U$99") (pin "CKO") (pinfunction "CKO_CKO") (pintype "bidirectional"))
    )
    (net (code "201") (name "Net-(U$100-PadCKO)") (class "Default")
      (node (ref "U$100") (pin "CKO") (pinfunction "CKO_CKO") (pintype "bidirectional"))
      (node (ref "U$101") (pin "CKI") (pinfunction "CKI_CKI") (pintype "bidirectional"))
    )
    (net (code "202") (name "Net-(U$100-PadSDI)") (class "Default")
      (node (ref "U$100") (pin "SDI") (pinfunction "SDI_SDI") (pintype "bidirectional"))
      (node (ref "U$99") (pin "SDO") (pinfunction "SDO_SDO") (pintype "bidirectional"))
    )
    (net (code "203") (name "Net-(U$100-PadSDO)") (class "Default")
      (node (ref "U$100") (pin "SDO") (pinfunction "SDO_SDO") (pintype "bidirectional"))
      (node (ref "U$101") (pin "SDI") (pinfunction "SDI_SDI") (pintype "bidirectional"))
    )
    (net (code "204") (name "Net-(U$101-PadCKO)") (class "Default")
      (node (ref "U$101") (pin "CKO") (pinfunction "CKO_CKO") (pintype "bidirectional"))
      (node (ref "U$102") (pin "CKI") (pinfunction "CKI_CKI") (pintype "bidirectional"))
    )
    (net (code "205") (name "Net-(U$101-PadSDO)") (class "Default")
      (node (ref "U$101") (pin "SDO") (pinfunction "SDO_SDO") (pintype "bidirectional"))
      (node (ref "U$102") (pin "SDI") (pinfunction "SDI_SDI") (pintype "bidirectional"))
    )
    (net (code "206") (name "Net-(U$102-PadCKO)") (class "Default")
      (node (ref "U$102") (pin "CKO") (pinfunction "CKO_CKO") (pintype "bidirectional"))
      (node (ref "U$103") (pin "CKI") (pinfunction "CKI_CKI") (pintype "bidirectional"))
    )
    (net (code "207") (name "Net-(U$102-PadSDO)") (class "Default")
      (node (ref "U$102") (pin "SDO") (pinfunction "SDO_SDO") (pintype "bidirectional"))
      (node (ref "U$103") (pin "SDI") (pinfunction "SDI_SDI") (pintype "bidirectional"))
    )
    (net (code "208") (name "Net-(U$103-PadCKO)") (class "Default")
      (node (ref "U$103") (pin "CKO") (pinfunction "CKO_CKO") (pintype "bidirectional"))
      (node (ref "U$104") (pin "CKI") (pinfunction "CKI_CKI") (pintype "bidirectional"))
    )
    (net (code "209") (name "Net-(U$103-PadSDO)") (class "Default")
      (node (ref "U$103") (pin "SDO") (pinfunction "SDO_SDO") (pintype "bidirectional"))
      (node (ref "U$104") (pin "SDI") (pinfunction "SDI_SDI") (pintype "bidirectional"))
    )
    (net (code "210") (name "Net-(U$104-PadCKO)") (class "Default")
      (node (ref "U$104") (pin "CKO") (pinfunction "CKO_CKO") (pintype "bidirectional"))
      (node (ref "U$105") (pin "CKI") (pinfunction "CKI_CKI") (pintype "bidirectional"))
    )
    (net (code "211") (name "Net-(U$104-PadSDO)") (class "Default")
      (node (ref "U$104") (pin "SDO") (pinfunction "SDO_SDO") (pintype "bidirectional"))
      (node (ref "U$105") (pin "SDI") (pinfunction "SDI_SDI") (pintype "bidirectional"))
    )
    (net (code "212") (name "Net-(U$105-PadCKO)") (class "Default")
      (node (ref "U$105") (pin "CKO") (pinfunction "CKO_CKO") (pintype "bidirectional"))
      (node (ref "U$106") (pin "CKI") (pinfunction "CKI_CKI") (pintype "bidirectional"))
    )
    (net (code "213") (name "Net-(U$105-PadSDO)") (class "Default")
      (node (ref "U$105") (pin "SDO") (pinfunction "SDO_SDO") (pintype "bidirectional"))
      (node (ref "U$106") (pin "SDI") (pinfunction "SDI_SDI") (pintype "bidirectional"))
    )
    (net (code "214") (name "Net-(U$106-PadCKO)") (class "Default")
      (node (ref "U$106") (pin "CKO") (pinfunction "CKO_CKO") (pintype "bidirectional"))
      (node (ref "U$107") (pin "CKI") (pinfunction "CKI_CKI") (pintype "bidirectional"))
    )
    (net (code "215") (name "Net-(U$106-PadSDO)") (class "Default")
      (node (ref "U$106") (pin "SDO") (pinfunction "SDO_SDO") (pintype "bidirectional"))
      (node (ref "U$107") (pin "SDI") (pinfunction "SDI_SDI") (pintype "bidirectional"))
    )
    (net (code "216") (name "Net-(U$107-PadCKO)") (class "Default")
      (node (ref "U$107") (pin "CKO") (pinfunction "CKO_CKO") (pintype "bidirectional"))
      (node (ref "U$108") (pin "CKI") (pinfunction "CKI_CKI") (pintype "bidirectional"))
    )
    (net (code "217") (name "Net-(U$107-PadSDO)") (class "Default")
      (node (ref "U$107") (pin "SDO") (pinfunction "SDO_SDO") (pintype "bidirectional"))
      (node (ref "U$108") (pin "SDI") (pinfunction "SDI_SDI") (pintype "bidirectional"))
    )
    (net (code "218") (name "Net-(U$108-PadCKO)") (class "Default")
      (node (ref "U$108") (pin "CKO") (pinfunction "CKO_CKO") (pintype "bidirectional"))
      (node (ref "U$109") (pin "CKI") (pinfunction "CKI_CKI") (pintype "bidirectional"))
    )
    (net (code "219") (name "Net-(U$108-PadSDO)") (class "Default")
      (node (ref "U$108") (pin "SDO") (pinfunction "SDO_SDO") (pintype "bidirectional"))
      (node (ref "U$109") (pin "SDI") (pinfunction "SDI_SDI") (pintype "bidirectional"))
    )
    (net (code "220") (name "Net-(U$109-PadCKO)") (class "Default")
      (node (ref "U$109") (pin "CKO") (pinfunction "CKO_CKO") (pintype "bidirectional"))
      (node (ref "U$110") (pin "CKI") (pinfunction "CKI_CKI") (pintype "bidirectional"))
    )
    (net (code "221") (name "Net-(U$109-PadSDO)") (class "Default")
      (node (ref "U$109") (pin "SDO") (pinfunction "SDO_SDO") (pintype "bidirectional"))
      (node (ref "U$110") (pin "SDI") (pinfunction "SDI_SDI") (pintype "bidirectional"))
    )
    (net (code "222") (name "Net-(U$110-PadCKO)") (class "Default")
      (node (ref "U$110") (pin "CKO") (pinfunction "CKO_CKO") (pintype "bidirectional"))
      (node (ref "U$111") (pin "CKI") (pinfunction "CKI_CKI") (pintype "bidirectional"))
    )
    (net (code "223") (name "Net-(U$110-PadSDO)") (class "Default")
      (node (ref "U$110") (pin "SDO") (pinfunction "SDO_SDO") (pintype "bidirectional"))
      (node (ref "U$111") (pin "SDI") (pinfunction "SDI_SDI") (pintype "bidirectional"))
    )
    (net (code "224") (name "Net-(U$111-PadCKO)") (class "Default")
      (node (ref "U$111") (pin "CKO") (pinfunction "CKO_CKO") (pintype "bidirectional"))
      (node (ref "U$112") (pin "CKI") (pinfunction "CKI_CKI") (pintype "bidirectional"))
    )
    (net (code "225") (name "Net-(U$111-PadSDO)") (class "Default")
      (node (ref "U$111") (pin "SDO") (pinfunction "SDO_SDO") (pintype "bidirectional"))
      (node (ref "U$112") (pin "SDI") (pinfunction "SDI_SDI") (pintype "bidirectional"))
    )
    (net (code "226") (name "Net-(U$112-PadCKO)") (class "Default")
      (node (ref "U$112") (pin "CKO") (pinfunction "CKO_CKO") (pintype "bidirectional"))
      (node (ref "U$113") (pin "CKI") (pinfunction "CKI_CKI") (pintype "bidirectional"))
    )
    (net (code "227") (name "Net-(U$112-PadSDO)") (class "Default")
      (node (ref "U$112") (pin "SDO") (pinfunction "SDO_SDO") (pintype "bidirectional"))
      (node (ref "U$113") (pin "SDI") (pinfunction "SDI_SDI") (pintype "bidirectional"))
    )
    (net (code "228") (name "Net-(U$113-PadCKO)") (class "Default")
      (node (ref "U$113") (pin "CKO") (pinfunction "CKO_CKO") (pintype "bidirectional"))
      (node (ref "U$114") (pin "CKI") (pinfunction "CKI_CKI") (pintype "bidirectional"))
    )
    (net (code "229") (name "Net-(U$113-PadSDO)") (class "Default")
      (node (ref "U$113") (pin "SDO") (pinfunction "SDO_SDO") (pintype "bidirectional"))
      (node (ref "U$114") (pin "SDI") (pinfunction "SDI_SDI") (pintype "bidirectional"))
    )
    (net (code "230") (name "Net-(U$114-PadCKO)") (class "Default")
      (node (ref "U$114") (pin "CKO") (pinfunction "CKO_CKO") (pintype "bidirectional"))
      (node (ref "U$115") (pin "CKI") (pinfunction "CKI_CKI") (pintype "bidirectional"))
    )
    (net (code "231") (name "Net-(U$114-PadSDO)") (class "Default")
      (node (ref "U$114") (pin "SDO") (pinfunction "SDO_SDO") (pintype "bidirectional"))
      (node (ref "U$115") (pin "SDI") (pinfunction "SDI_SDI") (pintype "bidirectional"))
    )
    (net (code "232") (name "Net-(U$115-PadCKO)") (class "Default")
      (node (ref "U$115") (pin "CKO") (pinfunction "CKO_CKO") (pintype "bidirectional"))
      (node (ref "U$116") (pin "CKI") (pinfunction "CKI_CKI") (pintype "bidirectional"))
    )
    (net (code "233") (name "Net-(U$115-PadSDO)") (class "Default")
      (node (ref "U$115") (pin "SDO") (pinfunction "SDO_SDO") (pintype "bidirectional"))
      (node (ref "U$116") (pin "SDI") (pinfunction "SDI_SDI") (pintype "bidirectional"))
    )
    (net (code "234") (name "Net-(U$116-PadCKO)") (class "Default")
      (node (ref "U$116") (pin "CKO") (pinfunction "CKO_CKO") (pintype "bidirectional"))
      (node (ref "U$117") (pin "CKI") (pinfunction "CKI_CKI") (pintype "bidirectional"))
    )
    (net (code "235") (name "Net-(U$116-PadSDO)") (class "Default")
      (node (ref "U$116") (pin "SDO") (pinfunction "SDO_SDO") (pintype "bidirectional"))
      (node (ref "U$117") (pin "SDI") (pinfunction "SDI_SDI") (pintype "bidirectional"))
    )
    (net (code "236") (name "Net-(U$117-PadCKO)") (class "Default")
      (node (ref "U$117") (pin "CKO") (pinfunction "CKO_CKO") (pintype "bidirectional"))
      (node (ref "U$118") (pin "CKI") (pinfunction "CKI_CKI") (pintype "bidirectional"))
    )
    (net (code "237") (name "Net-(U$117-PadSDO)") (class "Default")
      (node (ref "U$117") (pin "SDO") (pinfunction "SDO_SDO") (pintype "bidirectional"))
      (node (ref "U$118") (pin "SDI") (pinfunction "SDI_SDI") (pintype "bidirectional"))
    )
    (net (code "238") (name "Net-(U$118-PadCKO)") (class "Default")
      (node (ref "U$118") (pin "CKO") (pinfunction "CKO_CKO") (pintype "bidirectional"))
      (node (ref "U$119") (pin "CKI") (pinfunction "CKI_CKI") (pintype "bidirectional"))
    )
    (net (code "239") (name "Net-(U$118-PadSDO)") (class "Default")
      (node (ref "U$118") (pin "SDO") (pinfunction "SDO_SDO") (pintype "bidirectional"))
      (node (ref "U$119") (pin "SDI") (pinfunction "SDI_SDI") (pintype "bidirectional"))
    )
    (net (code "240") (name "Net-(U$119-PadCKO)") (class "Default")
      (node (ref "U$119") (pin "CKO") (pinfunction "CKO_CKO") (pintype "bidirectional"))
      (node (ref "U$120") (pin "CKI") (pinfunction "CKI_CKI") (pintype "bidirectional"))
    )
    (net (code "241") (name "Net-(U$119-PadSDO)") (class "Default")
      (node (ref "U$119") (pin "SDO") (pinfunction "SDO_SDO") (pintype "bidirectional"))
      (node (ref "U$120") (pin "SDI") (pinfunction "SDI_SDI") (pintype "bidirectional"))
    )
    (net (code "242") (name "Net-(U$120-PadCKO)") (class "Default")
      (node (ref "U$120") (pin "CKO") (pinfunction "CKO_CKO") (pintype "bidirectional"))
      (node (ref "U$121") (pin "CKI") (pinfunction "CKI_CKI") (pintype "bidirectional"))
    )
    (net (code "243") (name "Net-(U$120-PadSDO)") (class "Default")
      (node (ref "U$120") (pin "SDO") (pinfunction "SDO_SDO") (pintype "bidirectional"))
      (node (ref "U$121") (pin "SDI") (pinfunction "SDI_SDI") (pintype "bidirectional"))
    )
    (net (code "244") (name "Net-(U$121-PadCKO)") (class "Default")
      (node (ref "U$121") (pin "CKO") (pinfunction "CKO_CKO") (pintype "bidirectional"))
      (node (ref "U$122") (pin "CKI") (pinfunction "CKI_CKI") (pintype "bidirectional"))
    )
    (net (code "245") (name "Net-(U$121-PadSDO)") (class "Default")
      (node (ref "U$121") (pin "SDO") (pinfunction "SDO_SDO") (pintype "bidirectional"))
      (node (ref "U$122") (pin "SDI") (pinfunction "SDI_SDI") (pintype "bidirectional"))
    )
    (net (code "246") (name "Net-(U$122-PadCKO)") (class "Default")
      (node (ref "U$122") (pin "CKO") (pinfunction "CKO_CKO") (pintype "bidirectional"))
      (node (ref "U$123") (pin "CKI") (pinfunction "CKI_CKI") (pintype "bidirectional"))
    )
    (net (code "247") (name "Net-(U$122-PadSDO)") (class "Default")
      (node (ref "U$122") (pin "SDO") (pinfunction "SDO_SDO") (pintype "bidirectional"))
      (node (ref "U$123") (pin "SDI") (pinfunction "SDI_SDI") (pintype "bidirectional"))
    )
    (net (code "248") (name "Net-(U$123-PadCKO)") (class "Default")
      (node (ref "U$123") (pin "CKO") (pinfunction "CKO_CKO") (pintype "bidirectional"))
      (node (ref "U$124") (pin "CKI") (pinfunction "CKI_CKI") (pintype "bidirectional"))
    )
    (net (code "249") (name "Net-(U$123-PadSDO)") (class "Default")
      (node (ref "U$123") (pin "SDO") (pinfunction "SDO_SDO") (pintype "bidirectional"))
      (node (ref "U$124") (pin "SDI") (pinfunction "SDI_SDI") (pintype "bidirectional"))
    )
    (net (code "250") (name "Net-(U$124-PadCKO)") (class "Default")
      (node (ref "U$124") (pin "CKO") (pinfunction "CKO_CKO") (pintype "bidirectional"))
      (node (ref "U$125") (pin "CKI") (pinfunction "CKI_CKI") (pintype "bidirectional"))
    )
    (net (code "251") (name "Net-(U$124-PadSDO)") (class "Default")
      (node (ref "U$124") (pin "SDO") (pinfunction "SDO_SDO") (pintype "bidirectional"))
      (node (ref "U$125") (pin "SDI") (pinfunction "SDI_SDI") (pintype "bidirectional"))
    )
    (net (code "252") (name "Net-(U$125-PadCKO)") (class "Default")
      (node (ref "U$125") (pin "CKO") (pinfunction "CKO_CKO") (pintype "bidirectional"))
      (node (ref "U$126") (pin "CKI") (pinfunction "CKI_CKI") (pintype "bidirectional"))
    )
    (net (code "253") (name "Net-(U$125-PadSDO)") (class "Default")
      (node (ref "U$125") (pin "SDO") (pinfunction "SDO_SDO") (pintype "bidirectional"))
      (node (ref "U$126") (pin "SDI") (pinfunction "SDI_SDI") (pintype "bidirectional"))
    )
    (net (code "254") (name "Net-(U$126-PadCKO)") (class "Default")
      (node (ref "U$126") (pin "CKO") (pinfunction "CKO_CKO") (pintype "bidirectional"))
      (node (ref "U$127") (pin "CKI") (pinfunction "CKI_CKI") (pintype "bidirectional"))
    )
    (net (code "255") (name "Net-(U$126-PadSDO)") (class "Default")
      (node (ref "U$126") (pin "SDO") (pinfunction "SDO_SDO") (pintype "bidirectional"))
      (node (ref "U$127") (pin "SDI") (pinfunction "SDI_SDI") (pintype "bidirectional"))
    )
    (net (code "256") (name "Net-(U$127-PadCKO)") (class "Default")
      (node (ref "U$127") (pin "CKO") (pinfunction "CKO_CKO") (pintype "bidirectional"))
      (node (ref "U$128") (pin "CKI") (pinfunction "CKI_CKI") (pintype "bidirectional"))
    )
    (net (code "257") (name "Net-(U$127-PadSDO)") (class "Default")
      (node (ref "U$127") (pin "SDO") (pinfunction "SDO_SDO") (pintype "bidirectional"))
      (node (ref "U$128") (pin "SDI") (pinfunction "SDI_SDI") (pintype "bidirectional"))
    )
    (net (code "258") (name "Net-(U$128-PadCKO)") (class "Default")
      (node (ref "U$128") (pin "CKO") (pinfunction "CKO_CKO") (pintype "bidirectional"))
      (node (ref "U$129") (pin "CKI") (pinfunction "CKI_CKI") (pintype "bidirectional"))
    )
    (net (code "259") (name "Net-(U$128-PadSDO)") (class "Default")
      (node (ref "U$128") (pin "SDO") (pinfunction "SDO_SDO") (pintype "bidirectional"))
      (node (ref "U$129") (pin "SDI") (pinfunction "SDI_SDI") (pintype "bidirectional"))
    )
    (net (code "260") (name "Net-(U$129-PadCKO)") (class "Default")
      (node (ref "U$129") (pin "CKO") (pinfunction "CKO_CKO") (pintype "bidirectional"))
      (node (ref "U$130") (pin "CKI") (pinfunction "CKI_CKI") (pintype "bidirectional"))
    )
    (net (code "261") (name "Net-(U$129-PadSDO)") (class "Default")
      (node (ref "U$129") (pin "SDO") (pinfunction "SDO_SDO") (pintype "bidirectional"))
      (node (ref "U$130") (pin "SDI") (pinfunction "SDI_SDI") (pintype "bidirectional"))
    )
    (net (code "262") (name "Net-(U$130-PadCKO)") (class "Default")
      (node (ref "U$130") (pin "CKO") (pinfunction "CKO_CKO") (pintype "bidirectional"))
      (node (ref "U$131") (pin "CKI") (pinfunction "CKI_CKI") (pintype "bidirectional"))
    )
    (net (code "263") (name "Net-(U$130-PadSDO)") (class "Default")
      (node (ref "U$130") (pin "SDO") (pinfunction "SDO_SDO") (pintype "bidirectional"))
      (node (ref "U$131") (pin "SDI") (pinfunction "SDI_SDI") (pintype "bidirectional"))
    )
    (net (code "264") (name "Net-(U$131-PadCKO)") (class "Default")
      (node (ref "U$131") (pin "CKO") (pinfunction "CKO_CKO") (pintype "bidirectional"))
      (node (ref "U$132") (pin "CKI") (pinfunction "CKI_CKI") (pintype "bidirectional"))
    )
    (net (code "265") (name "Net-(U$131-PadSDO)") (class "Default")
      (node (ref "U$131") (pin "SDO") (pinfunction "SDO_SDO") (pintype "bidirectional"))
      (node (ref "U$132") (pin "SDI") (pinfunction "SDI_SDI") (pintype "bidirectional"))
    )
    (net (code "266") (name "Net-(U$132-PadCKO)") (class "Default")
      (node (ref "U$132") (pin "CKO") (pinfunction "CKO_CKO") (pintype "bidirectional"))
      (node (ref "U$133") (pin "CKI") (pinfunction "CKI_CKI") (pintype "bidirectional"))
    )
    (net (code "267") (name "Net-(U$132-PadSDO)") (class "Default")
      (node (ref "U$132") (pin "SDO") (pinfunction "SDO_SDO") (pintype "bidirectional"))
      (node (ref "U$133") (pin "SDI") (pinfunction "SDI_SDI") (pintype "bidirectional"))
    )
    (net (code "268") (name "Net-(U$133-PadCKO)") (class "Default")
      (node (ref "U$133") (pin "CKO") (pinfunction "CKO_CKO") (pintype "bidirectional"))
      (node (ref "U$134") (pin "CKI") (pinfunction "CKI_CKI") (pintype "bidirectional"))
    )
    (net (code "269") (name "Net-(U$133-PadSDO)") (class "Default")
      (node (ref "U$133") (pin "SDO") (pinfunction "SDO_SDO") (pintype "bidirectional"))
      (node (ref "U$134") (pin "SDI") (pinfunction "SDI_SDI") (pintype "bidirectional"))
    )
    (net (code "270") (name "Net-(U$134-PadCKO)") (class "Default")
      (node (ref "U$134") (pin "CKO") (pinfunction "CKO_CKO") (pintype "bidirectional"))
      (node (ref "U$135") (pin "CKI") (pinfunction "CKI_CKI") (pintype "bidirectional"))
    )
    (net (code "271") (name "Net-(U$134-PadSDO)") (class "Default")
      (node (ref "U$134") (pin "SDO") (pinfunction "SDO_SDO") (pintype "bidirectional"))
      (node (ref "U$135") (pin "SDI") (pinfunction "SDI_SDI") (pintype "bidirectional"))
    )
    (net (code "272") (name "Net-(U$135-PadCKO)") (class "Default")
      (node (ref "U$135") (pin "CKO") (pinfunction "CKO_CKO") (pintype "bidirectional"))
      (node (ref "U$136") (pin "CKI") (pinfunction "CKI_CKI") (pintype "bidirectional"))
    )
    (net (code "273") (name "Net-(U$135-PadSDO)") (class "Default")
      (node (ref "U$135") (pin "SDO") (pinfunction "SDO_SDO") (pintype "bidirectional"))
      (node (ref "U$136") (pin "SDI") (pinfunction "SDI_SDI") (pintype "bidirectional"))
    )
    (net (code "274") (name "Net-(U$136-PadCKO)") (class "Default")
      (node (ref "U$136") (pin "CKO") (pinfunction "CKO_CKO") (pintype "bidirectional"))
      (node (ref "U$137") (pin "CKI") (pinfunction "CKI_CKI") (pintype "bidirectional"))
    )
    (net (code "275") (name "Net-(U$136-PadSDO)") (class "Default")
      (node (ref "U$136") (pin "SDO") (pinfunction "SDO_SDO") (pintype "bidirectional"))
      (node (ref "U$137") (pin "SDI") (pinfunction "SDI_SDI") (pintype "bidirectional"))
    )
    (net (code "276") (name "Net-(U$137-PadCKO)") (class "Default")
      (node (ref "U$137") (pin "CKO") (pinfunction "CKO_CKO") (pintype "bidirectional"))
      (node (ref "U$138") (pin "CKI") (pinfunction "CKI_CKI") (pintype "bidirectional"))
    )
    (net (code "277") (name "Net-(U$137-PadSDO)") (class "Default")
      (node (ref "U$137") (pin "SDO") (pinfunction "SDO_SDO") (pintype "bidirectional"))
      (node (ref "U$138") (pin "SDI") (pinfunction "SDI_SDI") (pintype "bidirectional"))
    )
    (net (code "278") (name "Net-(U$138-PadCKO)") (class "Default")
      (node (ref "U$138") (pin "CKO") (pinfunction "CKO_CKO") (pintype "bidirectional"))
      (node (ref "U$139") (pin "CKI") (pinfunction "CKI_CKI") (pintype "bidirectional"))
    )
    (net (code "279") (name "Net-(U$138-PadSDO)") (class "Default")
      (node (ref "U$138") (pin "SDO") (pinfunction "SDO_SDO") (pintype "bidirectional"))
      (node (ref "U$139") (pin "SDI") (pinfunction "SDI_SDI") (pintype "bidirectional"))
    )
    (net (code "280") (name "Net-(U$139-PadCKO)") (class "Default")
      (node (ref "U$139") (pin "CKO") (pinfunction "CKO_CKO") (pintype "bidirectional"))
      (node (ref "U$140") (pin "CKI") (pinfunction "CKI_CKI") (pintype "bidirectional"))
    )
    (net (code "281") (name "Net-(U$139-PadSDO)") (class "Default")
      (node (ref "U$139") (pin "SDO") (pinfunction "SDO_SDO") (pintype "bidirectional"))
      (node (ref "U$140") (pin "SDI") (pinfunction "SDI_SDI") (pintype "bidirectional"))
    )
    (net (code "282") (name "Net-(U$140-PadCKO)") (class "Default")
      (node (ref "U$140") (pin "CKO") (pinfunction "CKO_CKO") (pintype "bidirectional"))
      (node (ref "U$141") (pin "CKI") (pinfunction "CKI_CKI") (pintype "bidirectional"))
    )
    (net (code "283") (name "Net-(U$140-PadSDO)") (class "Default")
      (node (ref "U$140") (pin "SDO") (pinfunction "SDO_SDO") (pintype "bidirectional"))
      (node (ref "U$141") (pin "SDI") (pinfunction "SDI_SDI") (pintype "bidirectional"))
    )
    (net (code "284") (name "Net-(U$141-PadCKO)") (class "Default")
      (node (ref "U$141") (pin "CKO") (pinfunction "CKO_CKO") (pintype "bidirectional"))
      (node (ref "U$142") (pin "CKI") (pinfunction "CKI_CKI") (pintype "bidirectional"))
    )
    (net (code "285") (name "Net-(U$141-PadSDO)") (class "Default")
      (node (ref "U$141") (pin "SDO") (pinfunction "SDO_SDO") (pintype "bidirectional"))
      (node (ref "U$142") (pin "SDI") (pinfunction "SDI_SDI") (pintype "bidirectional"))
    )
    (net (code "286") (name "Net-(U$142-PadCKO)") (class "Default")
      (node (ref "U$142") (pin "CKO") (pinfunction "CKO_CKO") (pintype "bidirectional"))
      (node (ref "U$143") (pin "CKI") (pinfunction "CKI_CKI") (pintype "bidirectional"))
    )
    (net (code "287") (name "Net-(U$142-PadSDO)") (class "Default")
      (node (ref "U$142") (pin "SDO") (pinfunction "SDO_SDO") (pintype "bidirectional"))
      (node (ref "U$143") (pin "SDI") (pinfunction "SDI_SDI") (pintype "bidirectional"))
    )
    (net (code "288") (name "Net-(U$143-PadCKO)") (class "Default")
      (node (ref "U$143") (pin "CKO") (pinfunction "CKO_CKO") (pintype "bidirectional"))
      (node (ref "U$144") (pin "CKI") (pinfunction "CKI_CKI") (pintype "bidirectional"))
    )
    (net (code "289") (name "Net-(U$143-PadSDO)") (class "Default")
      (node (ref "U$143") (pin "SDO") (pinfunction "SDO_SDO") (pintype "bidirectional"))
      (node (ref "U$144") (pin "SDI") (pinfunction "SDI_SDI") (pintype "bidirectional"))
    )
    (net (code "290") (name "Net-(U$144-PadCKO)") (class "Default")
      (node (ref "U$144") (pin "CKO") (pinfunction "CKO_CKO") (pintype "bidirectional"))
      (node (ref "U$145") (pin "CKI") (pinfunction "CKI_CKI") (pintype "bidirectional"))
    )
    (net (code "291") (name "Net-(U$144-PadSDO)") (class "Default")
      (node (ref "U$144") (pin "SDO") (pinfunction "SDO_SDO") (pintype "bidirectional"))
      (node (ref "U$145") (pin "SDI") (pinfunction "SDI_SDI") (pintype "bidirectional"))
    )
    (net (code "292") (name "Net-(U$145-PadCKO)") (class "Default")
      (node (ref "U$145") (pin "CKO") (pinfunction "CKO_CKO") (pintype "bidirectional"))
      (node (ref "U$146") (pin "CKI") (pinfunction "CKI_CKI") (pintype "bidirectional"))
    )
    (net (code "293") (name "Net-(U$145-PadSDO)") (class "Default")
      (node (ref "U$145") (pin "SDO") (pinfunction "SDO_SDO") (pintype "bidirectional"))
      (node (ref "U$146") (pin "SDI") (pinfunction "SDI_SDI") (pintype "bidirectional"))
    )
    (net (code "294") (name "Net-(U$146-PadCKO)") (class "Default")
      (node (ref "U$146") (pin "CKO") (pinfunction "CKO_CKO") (pintype "bidirectional"))
      (node (ref "U$147") (pin "CKI") (pinfunction "CKI_CKI") (pintype "bidirectional"))
    )
    (net (code "295") (name "Net-(U$146-PadSDO)") (class "Default")
      (node (ref "U$146") (pin "SDO") (pinfunction "SDO_SDO") (pintype "bidirectional"))
      (node (ref "U$147") (pin "SDI") (pinfunction "SDI_SDI") (pintype "bidirectional"))
    )
    (net (code "296") (name "Net-(U$147-PadCKO)") (class "Default")
      (node (ref "U$147") (pin "CKO") (pinfunction "CKO_CKO") (pintype "bidirectional"))
      (node (ref "U$148") (pin "CKI") (pinfunction "CKI_CKI") (pintype "bidirectional"))
    )
    (net (code "297") (name "Net-(U$147-PadSDO)") (class "Default")
      (node (ref "U$147") (pin "SDO") (pinfunction "SDO_SDO") (pintype "bidirectional"))
      (node (ref "U$148") (pin "SDI") (pinfunction "SDI_SDI") (pintype "bidirectional"))
    )
    (net (code "298") (name "VCC") (class "Default")
      (node (ref "U$1") (pin "VDD") (pinfunction "VDD_VDD") (pintype "bidirectional"))
      (node (ref "U$10") (pin "VDD") (pinfunction "VDD_VDD") (pintype "bidirectional"))
      (node (ref "U$100") (pin "VDD") (pinfunction "VDD_VDD") (pintype "bidirectional"))
      (node (ref "U$101") (pin "VDD") (pinfunction "VDD_VDD") (pintype "bidirectional"))
      (node (ref "U$102") (pin "VDD") (pinfunction "VDD_VDD") (pintype "bidirectional"))
      (node (ref "U$103") (pin "VDD") (pinfunction "VDD_VDD") (pintype "bidirectional"))
      (node (ref "U$104") (pin "VDD") (pinfunction "VDD_VDD") (pintype "bidirectional"))
      (node (ref "U$105") (pin "VDD") (pinfunction "VDD_VDD") (pintype "bidirectional"))
      (node (ref "U$106") (pin "VDD") (pinfunction "VDD_VDD") (pintype "bidirectional"))
      (node (ref "U$107") (pin "VDD") (pinfunction "VDD_VDD") (pintype "bidirectional"))
      (node (ref "U$108") (pin "VDD") (pinfunction "VDD_VDD") (pintype "bidirectional"))
      (node (ref "U$109") (pin "VDD") (pinfunction "VDD_VDD") (pintype "bidirectional"))
      (node (ref "U$11") (pin "VDD") (pinfunction "VDD_VDD") (pintype "bidirectional"))
      (node (ref "U$110") (pin "VDD") (pinfunction "VDD_VDD") (pintype "bidirectional"))
      (node (ref "U$111") (pin "VDD") (pinfunction "VDD_VDD") (pintype "bidirectional"))
      (node (ref "U$112") (pin "VDD") (pinfunction "VDD_VDD") (pintype "bidirectional"))
      (node (ref "U$113") (pin "VDD") (pinfunction "VDD_VDD") (pintype "bidirectional"))
      (node (ref "U$114") (pin "VDD") (pinfunction "VDD_VDD") (pintype "bidirectional"))
      (node (ref "U$115") (pin "VDD") (pinfunction "VDD_VDD") (pintype "bidirectional"))
      (node (ref "U$116") (pin "VDD") (pinfunction "VDD_VDD") (pintype "bidirectional"))
      (node (ref "U$117") (pin "VDD") (pinfunction "VDD_VDD") (pintype "bidirectional"))
      (node (ref "U$118") (pin "VDD") (pinfunction "VDD_VDD") (pintype "bidirectional"))
      (node (ref "U$119") (pin "VDD") (pinfunction "VDD_VDD") (pintype "bidirectional"))
      (node (ref "U$12") (pin "VDD") (pinfunction "VDD_VDD") (pintype "bidirectional"))
      (node (ref "U$120") (pin "VDD") (pinfunction "VDD_VDD") (pintype "bidirectional"))
      (node (ref "U$121") (pin "VDD") (pinfunction "VDD_VDD") (pintype "bidirectional"))
      (node (ref "U$122") (pin "VDD") (pinfunction "VDD_VDD") (pintype "bidirectional"))
      (node (ref "U$123") (pin "VDD") (pinfunction "VDD_VDD") (pintype "bidirectional"))
      (node (ref "U$124") (pin "VDD") (pinfunction "VDD_VDD") (pintype "bidirectional"))
      (node (ref "U$125") (pin "VDD") (pinfunction "VDD_VDD") (pintype "bidirectional"))
      (node (ref "U$126") (pin "VDD") (pinfunction "VDD_VDD") (pintype "bidirectional"))
      (node (ref "U$127") (pin "VDD") (pinfunction "VDD_VDD") (pintype "bidirectional"))
      (node (ref "U$128") (pin "VDD") (pinfunction "VDD_VDD") (pintype "bidirectional"))
      (node (ref "U$129") (pin "VDD") (pinfunction "VDD_VDD") (pintype "bidirectional"))
      (node (ref "U$13") (pin "VDD") (pinfunction "VDD_VDD") (pintype "bidirectional"))
      (node (ref "U$130") (pin "VDD") (pinfunction "VDD_VDD") (pintype "bidirectional"))
      (node (ref "U$131") (pin "VDD") (pinfunction "VDD_VDD") (pintype "bidirectional"))
      (node (ref "U$132") (pin "VDD") (pinfunction "VDD_VDD") (pintype "bidirectional"))
      (node (ref "U$133") (pin "VDD") (pinfunction "VDD_VDD") (pintype "bidirectional"))
      (node (ref "U$134") (pin "VDD") (pinfunction "VDD_VDD") (pintype "bidirectional"))
      (node (ref "U$135") (pin "VDD") (pinfunction "VDD_VDD") (pintype "bidirectional"))
      (node (ref "U$136") (pin "VDD") (pinfunction "VDD_VDD") (pintype "bidirectional"))
      (node (ref "U$137") (pin "VDD") (pinfunction "VDD_VDD") (pintype "bidirectional"))
      (node (ref "U$138") (pin "VDD") (pinfunction "VDD_VDD") (pintype "bidirectional"))
      (node (ref "U$139") (pin "VDD") (pinfunction "VDD_VDD") (pintype "bidirectional"))
      (node (ref "U$14") (pin "VDD") (pinfunction "VDD_VDD") (pintype "bidirectional"))
      (node (ref "U$140") (pin "VDD") (pinfunction "VDD_VDD") (pintype "bidirectional"))
      (node (ref "U$141") (pin "VDD") (pinfunction "VDD_VDD") (pintype "bidirectional"))
      (node (ref "U$142") (pin "VDD") (pinfunction "VDD_VDD") (pintype "bidirectional"))
      (node (ref "U$143") (pin "VDD") (pinfunction "VDD_VDD") (pintype "bidirectional"))
      (node (ref "U$144") (pin "VDD") (pinfunction "VDD_VDD") (pintype "bidirectional"))
      (node (ref "U$145") (pin "VDD") (pinfunction "VDD_VDD") (pintype "bidirectional"))
      (node (ref "U$146") (pin "VDD") (pinfunction "VDD_VDD") (pintype "bidirectional"))
      (node (ref "U$147") (pin "VDD") (pinfunction "VDD_VDD") (pintype "bidirectional"))
      (node (ref "U$148") (pin "VDD") (pinfunction "VDD_VDD") (pintype "bidirectional"))
      (node (ref "U$15") (pin "VDD") (pinfunction "VDD_VDD") (pintype "bidirectional"))
      (node (ref "U$16") (pin "VDD") (pinfunction "VDD_VDD") (pintype "bidirectional"))
      (node (ref "U$17") (pin "VDD") (pinfunction "VDD_VDD") (pintype "bidirectional"))
      (node (ref "U$18") (pin "VDD") (pinfunction "VDD_VDD") (pintype "bidirectional"))
      (node (ref "U$19") (pin "VDD") (pinfunction "VDD_VDD") (pintype "bidirectional"))
      (node (ref "U$2") (pin "VDD") (pinfunction "VDD_VDD") (pintype "bidirectional"))
      (node (ref "U$20") (pin "VDD") (pinfunction "VDD_VDD") (pintype "bidirectional"))
      (node (ref "U$21") (pin "VDD") (pinfunction "VDD_VDD") (pintype "bidirectional"))
      (node (ref "U$22") (pin "VDD") (pinfunction "VDD_VDD") (pintype "bidirectional"))
      (node (ref "U$23") (pin "VDD") (pinfunction "VDD_VDD") (pintype "bidirectional"))
      (node (ref "U$24") (pin "VDD") (pinfunction "VDD_VDD") (pintype "bidirectional"))
      (node (ref "U$25") (pin "VDD") (pinfunction "VDD_VDD") (pintype "bidirectional"))
      (node (ref "U$26") (pin "VDD") (pinfunction "VDD_VDD") (pintype "bidirectional"))
      (node (ref "U$27") (pin "VDD") (pinfunction "VDD_VDD") (pintype "bidirectional"))
      (node (ref "U$28") (pin "VDD") (pinfunction "VDD_VDD") (pintype "bidirectional"))
      (node (ref "U$29") (pin "VDD") (pinfunction "VDD_VDD") (pintype "bidirectional"))
      (node (ref "U$3") (pin "VDD") (pinfunction "VDD_VDD") (pintype "bidirectional"))
      (node (ref "U$30") (pin "VDD") (pinfunction "VDD_VDD") (pintype "bidirectional"))
      (node (ref "U$31") (pin "VDD") (pinfunction "VDD_VDD") (pintype "bidirectional"))
      (node (ref "U$32") (pin "VDD") (pinfunction "VDD_VDD") (pintype "bidirectional"))
      (node (ref "U$33") (pin "VDD") (pinfunction "VDD_VDD") (pintype "bidirectional"))
      (node (ref "U$34") (pin "VDD") (pinfunction "VDD_VDD") (pintype "bidirectional"))
      (node (ref "U$35") (pin "VDD") (pinfunction "VDD_VDD") (pintype "bidirectional"))
      (node (ref "U$36") (pin "VDD") (pinfunction "VDD_VDD") (pintype "bidirectional"))
      (node (ref "U$37") (pin "VDD") (pinfunction "VDD_VDD") (pintype "bidirectional"))
      (node (ref "U$38") (pin "VDD") (pinfunction "VDD_VDD") (pintype "bidirectional"))
      (node (ref "U$39") (pin "VDD") (pinfunction "VDD_VDD") (pintype "bidirectional"))
      (node (ref "U$4") (pin "VDD") (pinfunction "VDD_VDD") (pintype "bidirectional"))
      (node (ref "U$40") (pin "VDD") (pinfunction "VDD_VDD") (pintype "bidirectional"))
      (node (ref "U$41") (pin "VDD") (pinfunction "VDD_VDD") (pintype "bidirectional"))
      (node (ref "U$42") (pin "VDD") (pinfunction "VDD_VDD") (pintype "bidirectional"))
      (node (ref "U$43") (pin "VDD") (pinfunction "VDD_VDD") (pintype "bidirectional"))
      (node (ref "U$44") (pin "VDD") (pinfunction "VDD_VDD") (pintype "bidirectional"))
      (node (ref "U$45") (pin "VDD") (pinfunction "VDD_VDD") (pintype "bidirectional"))
      (node (ref "U$46") (pin "VDD") (pinfunction "VDD_VDD") (pintype "bidirectional"))
      (node (ref "U$47") (pin "VDD") (pinfunction "VDD_VDD") (pintype "bidirectional"))
      (node (ref "U$48") (pin "VDD") (pinfunction "VDD_VDD") (pintype "bidirectional"))
      (node (ref "U$49") (pin "VDD") (pinfunction "VDD_VDD") (pintype "bidirectional"))
      (node (ref "U$5") (pin "VDD") (pinfunction "VDD_VDD") (pintype "bidirectional"))
      (node (ref "U$50") (pin "VDD") (pinfunction "VDD_VDD") (pintype "bidirectional"))
      (node (ref "U$51") (pin "VDD") (pinfunction "VDD_VDD") (pintype "bidirectional"))
      (node (ref "U$52") (pin "VDD") (pinfunction "VDD_VDD") (pintype "bidirectional"))
      (node (ref "U$53") (pin "VDD") (pinfunction "VDD_VDD") (pintype "bidirectional"))
      (node (ref "U$54") (pin "VDD") (pinfunction "VDD_VDD") (pintype "bidirectional"))
      (node (ref "U$55") (pin "VDD") (pinfunction "VDD_VDD") (pintype "bidirectional"))
      (node (ref "U$56") (pin "VDD") (pinfunction "VDD_VDD") (pintype "bidirectional"))
      (node (ref "U$57") (pin "VDD") (pinfunction "VDD_VDD") (pintype "bidirectional"))
      (node (ref "U$58") (pin "VDD") (pinfunction "VDD_VDD") (pintype "bidirectional"))
      (node (ref "U$59") (pin "VDD") (pinfunction "VDD_VDD") (pintype "bidirectional"))
      (node (ref "U$6") (pin "VDD") (pinfunction "VDD_VDD") (pintype "bidirectional"))
      (node (ref "U$60") (pin "VDD") (pinfunction "VDD_VDD") (pintype "bidirectional"))
      (node (ref "U$61") (pin "VDD") (pinfunction "VDD_VDD") (pintype "bidirectional"))
      (node (ref "U$62") (pin "VDD") (pinfunction "VDD_VDD") (pintype "bidirectional"))
      (node (ref "U$63") (pin "VDD") (pinfunction "VDD_VDD") (pintype "bidirectional"))
      (node (ref "U$64") (pin "VDD") (pinfunction "VDD_VDD") (pintype "bidirectional"))
      (node (ref "U$65") (pin "VDD") (pinfunction "VDD_VDD") (pintype "bidirectional"))
      (node (ref "U$66") (pin "VDD") (pinfunction "VDD_VDD") (pintype "bidirectional"))
      (node (ref "U$67") (pin "VDD") (pinfunction "VDD_VDD") (pintype "bidirectional"))
      (node (ref "U$68") (pin "VDD") (pinfunction "VDD_VDD") (pintype "bidirectional"))
      (node (ref "U$69") (pin "VDD") (pinfunction "VDD_VDD") (pintype "bidirectional"))
      (node (ref "U$7") (pin "VDD") (pinfunction "VDD_VDD") (pintype "bidirectional"))
      (node (ref "U$70") (pin "VDD") (pinfunction "VDD_VDD") (pintype "bidirectional"))
      (node (ref "U$71") (pin "VDD") (pinfunction "VDD_VDD") (pintype "bidirectional"))
      (node (ref "U$72") (pin "VDD") (pinfunction "VDD_VDD") (pintype "bidirectional"))
      (node (ref "U$73") (pin "VDD") (pinfunction "VDD_VDD") (pintype "bidirectional"))
      (node (ref "U$74") (pin "VDD") (pinfunction "VDD_VDD") (pintype "bidirectional"))
      (node (ref "U$75") (pin "VDD") (pinfunction "VDD_VDD") (pintype "bidirectional"))
      (node (ref "U$76") (pin "VDD") (pinfunction "VDD_VDD") (pintype "bidirectional"))
      (node (ref "U$77") (pin "VDD") (pinfunction "VDD_VDD") (pintype "bidirectional"))
      (node (ref "U$78") (pin "VDD") (pinfunction "VDD_VDD") (pintype "bidirectional"))
      (node (ref "U$79") (pin "VDD") (pinfunction "VDD_VDD") (pintype "bidirectional"))
      (node (ref "U$8") (pin "VDD") (pinfunction "VDD_VDD") (pintype "bidirectional"))
      (node (ref "U$80") (pin "VDD") (pinfunction "VDD_VDD") (pintype "bidirectional"))
      (node (ref "U$81") (pin "VDD") (pinfunction "VDD_VDD") (pintype "bidirectional"))
      (node (ref "U$82") (pin "VDD") (pinfunction "VDD_VDD") (pintype "bidirectional"))
      (node (ref "U$83") (pin "VDD") (pinfunction "VDD_VDD") (pintype "bidirectional"))
      (node (ref "U$84") (pin "VDD") (pinfunction "VDD_VDD") (pintype "bidirectional"))
      (node (ref "U$85") (pin "VDD") (pinfunction "VDD_VDD") (pintype "bidirectional"))
      (node (ref "U$86") (pin "VDD") (pinfunction "VDD_VDD") (pintype "bidirectional"))
      (node (ref "U$87") (pin "VDD") (pinfunction "VDD_VDD") (pintype "bidirectional"))
      (node (ref "U$88") (pin "VDD") (pinfunction "VDD_VDD") (pintype "bidirectional"))
      (node (ref "U$89") (pin "VDD") (pinfunction "VDD_VDD") (pintype "bidirectional"))
      (node (ref "U$9") (pin "VDD") (pinfunction "VDD_VDD") (pintype "bidirectional"))
      (node (ref "U$90") (pin "VDD") (pinfunction "VDD_VDD") (pintype "bidirectional"))
      (node (ref "U$91") (pin "VDD") (pinfunction "VDD_VDD") (pintype "bidirectional"))
      (node (ref "U$92") (pin "VDD") (pinfunction "VDD_VDD") (pintype "bidirectional"))
      (node (ref "U$93") (pin "VDD") (pinfunction "VDD_VDD") (pintype "bidirectional"))
      (node (ref "U$94") (pin "VDD") (pinfunction "VDD_VDD") (pintype "bidirectional"))
      (node (ref "U$95") (pin "VDD") (pinfunction "VDD_VDD") (pintype "bidirectional"))
      (node (ref "U$96") (pin "VDD") (pinfunction "VDD_VDD") (pintype "bidirectional"))
      (node (ref "U$97") (pin "VDD") (pinfunction "VDD_VDD") (pintype "bidirectional"))
      (node (ref "U$98") (pin "VDD") (pinfunction "VDD_VDD") (pintype "bidirectional"))
      (node (ref "U$99") (pin "VDD") (pinfunction "VDD_VDD") (pintype "bidirectional"))
      (node (ref "VCC") (pin "1") (pinfunction "1_1") (pintype "passive"))
      (node (ref "VCC1") (pin "1") (pinfunction "1_1") (pintype "passive"))
      (node (ref "VCC2") (pin "1") (pinfunction "1_1") (pintype "passive"))
    )
    (net (code "299") (name "unconnected-(U$148-PadCKO)") (class "Default")
      (node (ref "U$148") (pin "CKO") (pinfunction "CKO_CKO") (pintype "bidirectional"))
    )
    (net (code "300") (name "unconnected-(U$148-PadSDO)") (class "Default")
      (node (ref "U$148") (pin "SDO") (pinfunction "SDO_SDO") (pintype "bidirectional"))
    )
  )
)
